# SOTB_Feb22.net
KiCad netlist of a schematic drawn in EAGLE
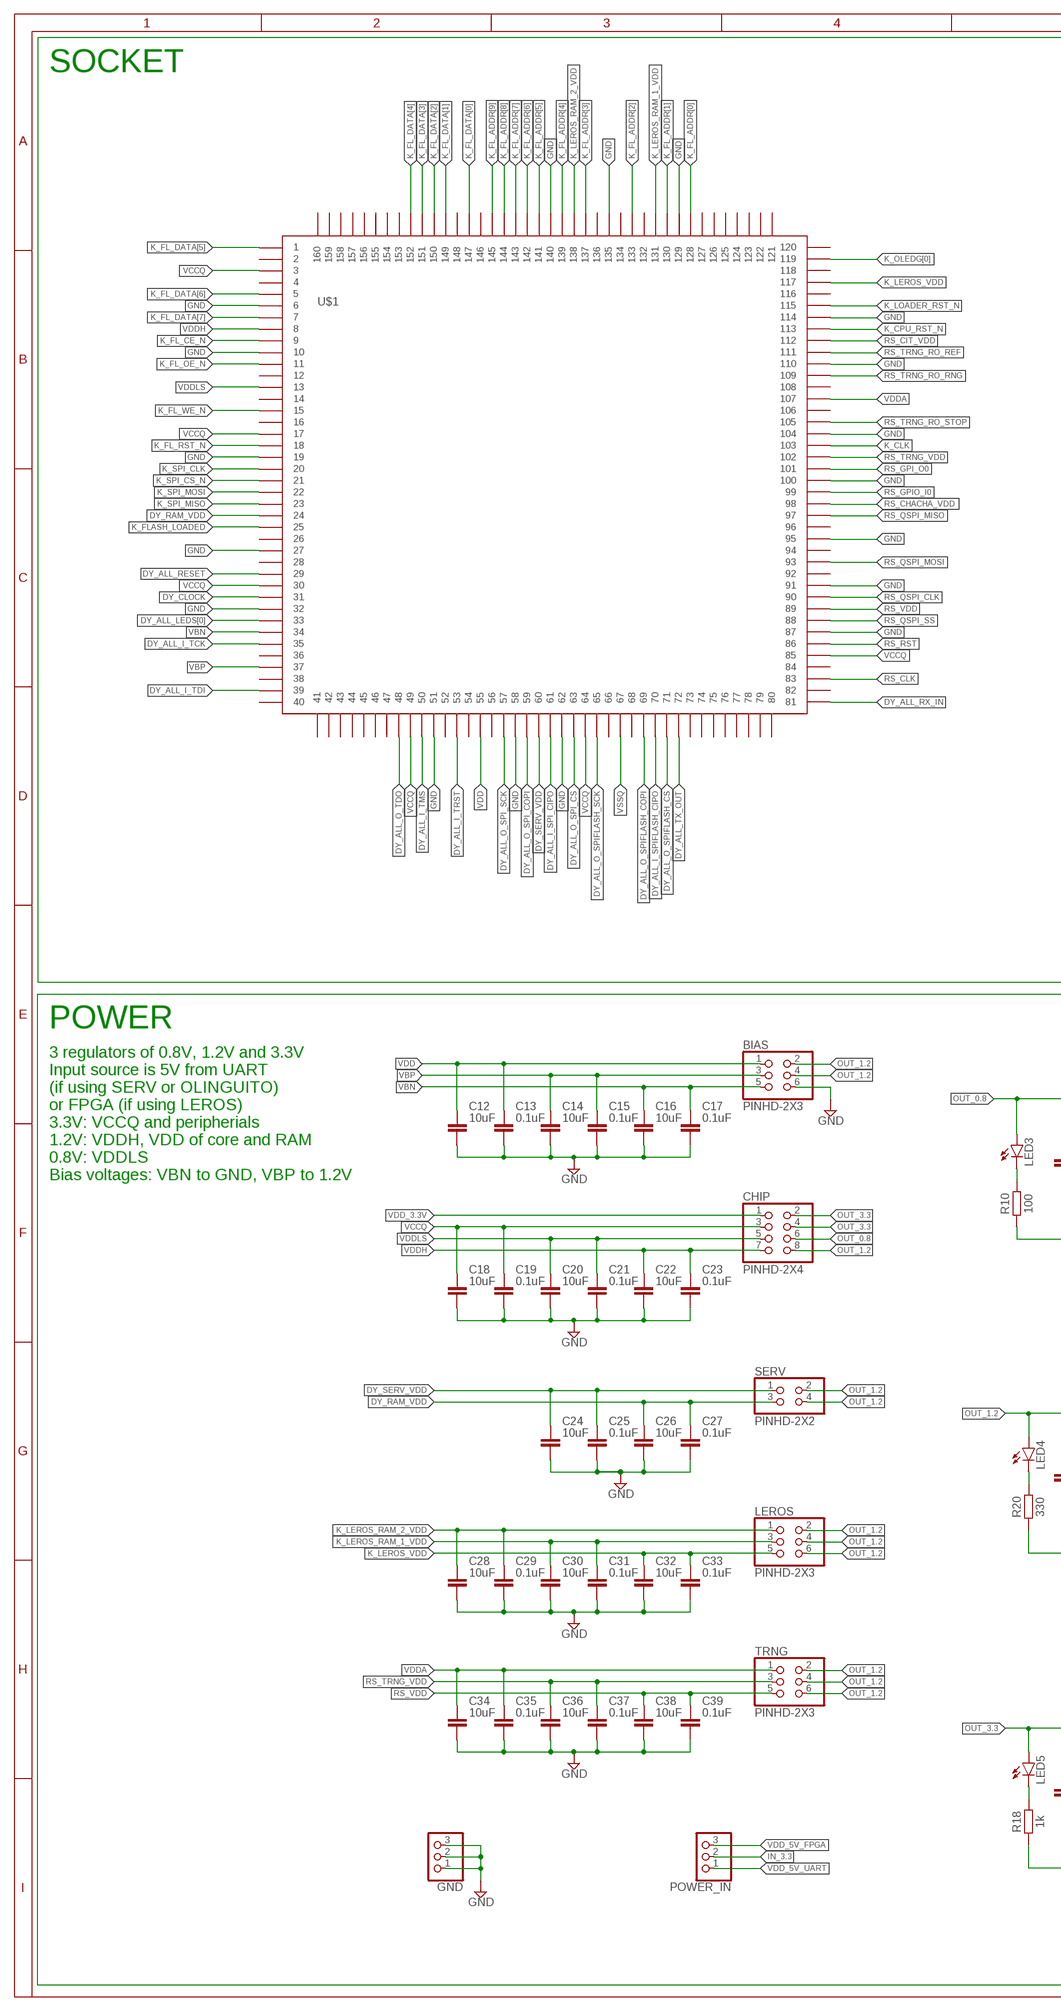
[diagram p0: schematic, sheet 1, part 1 of 2]
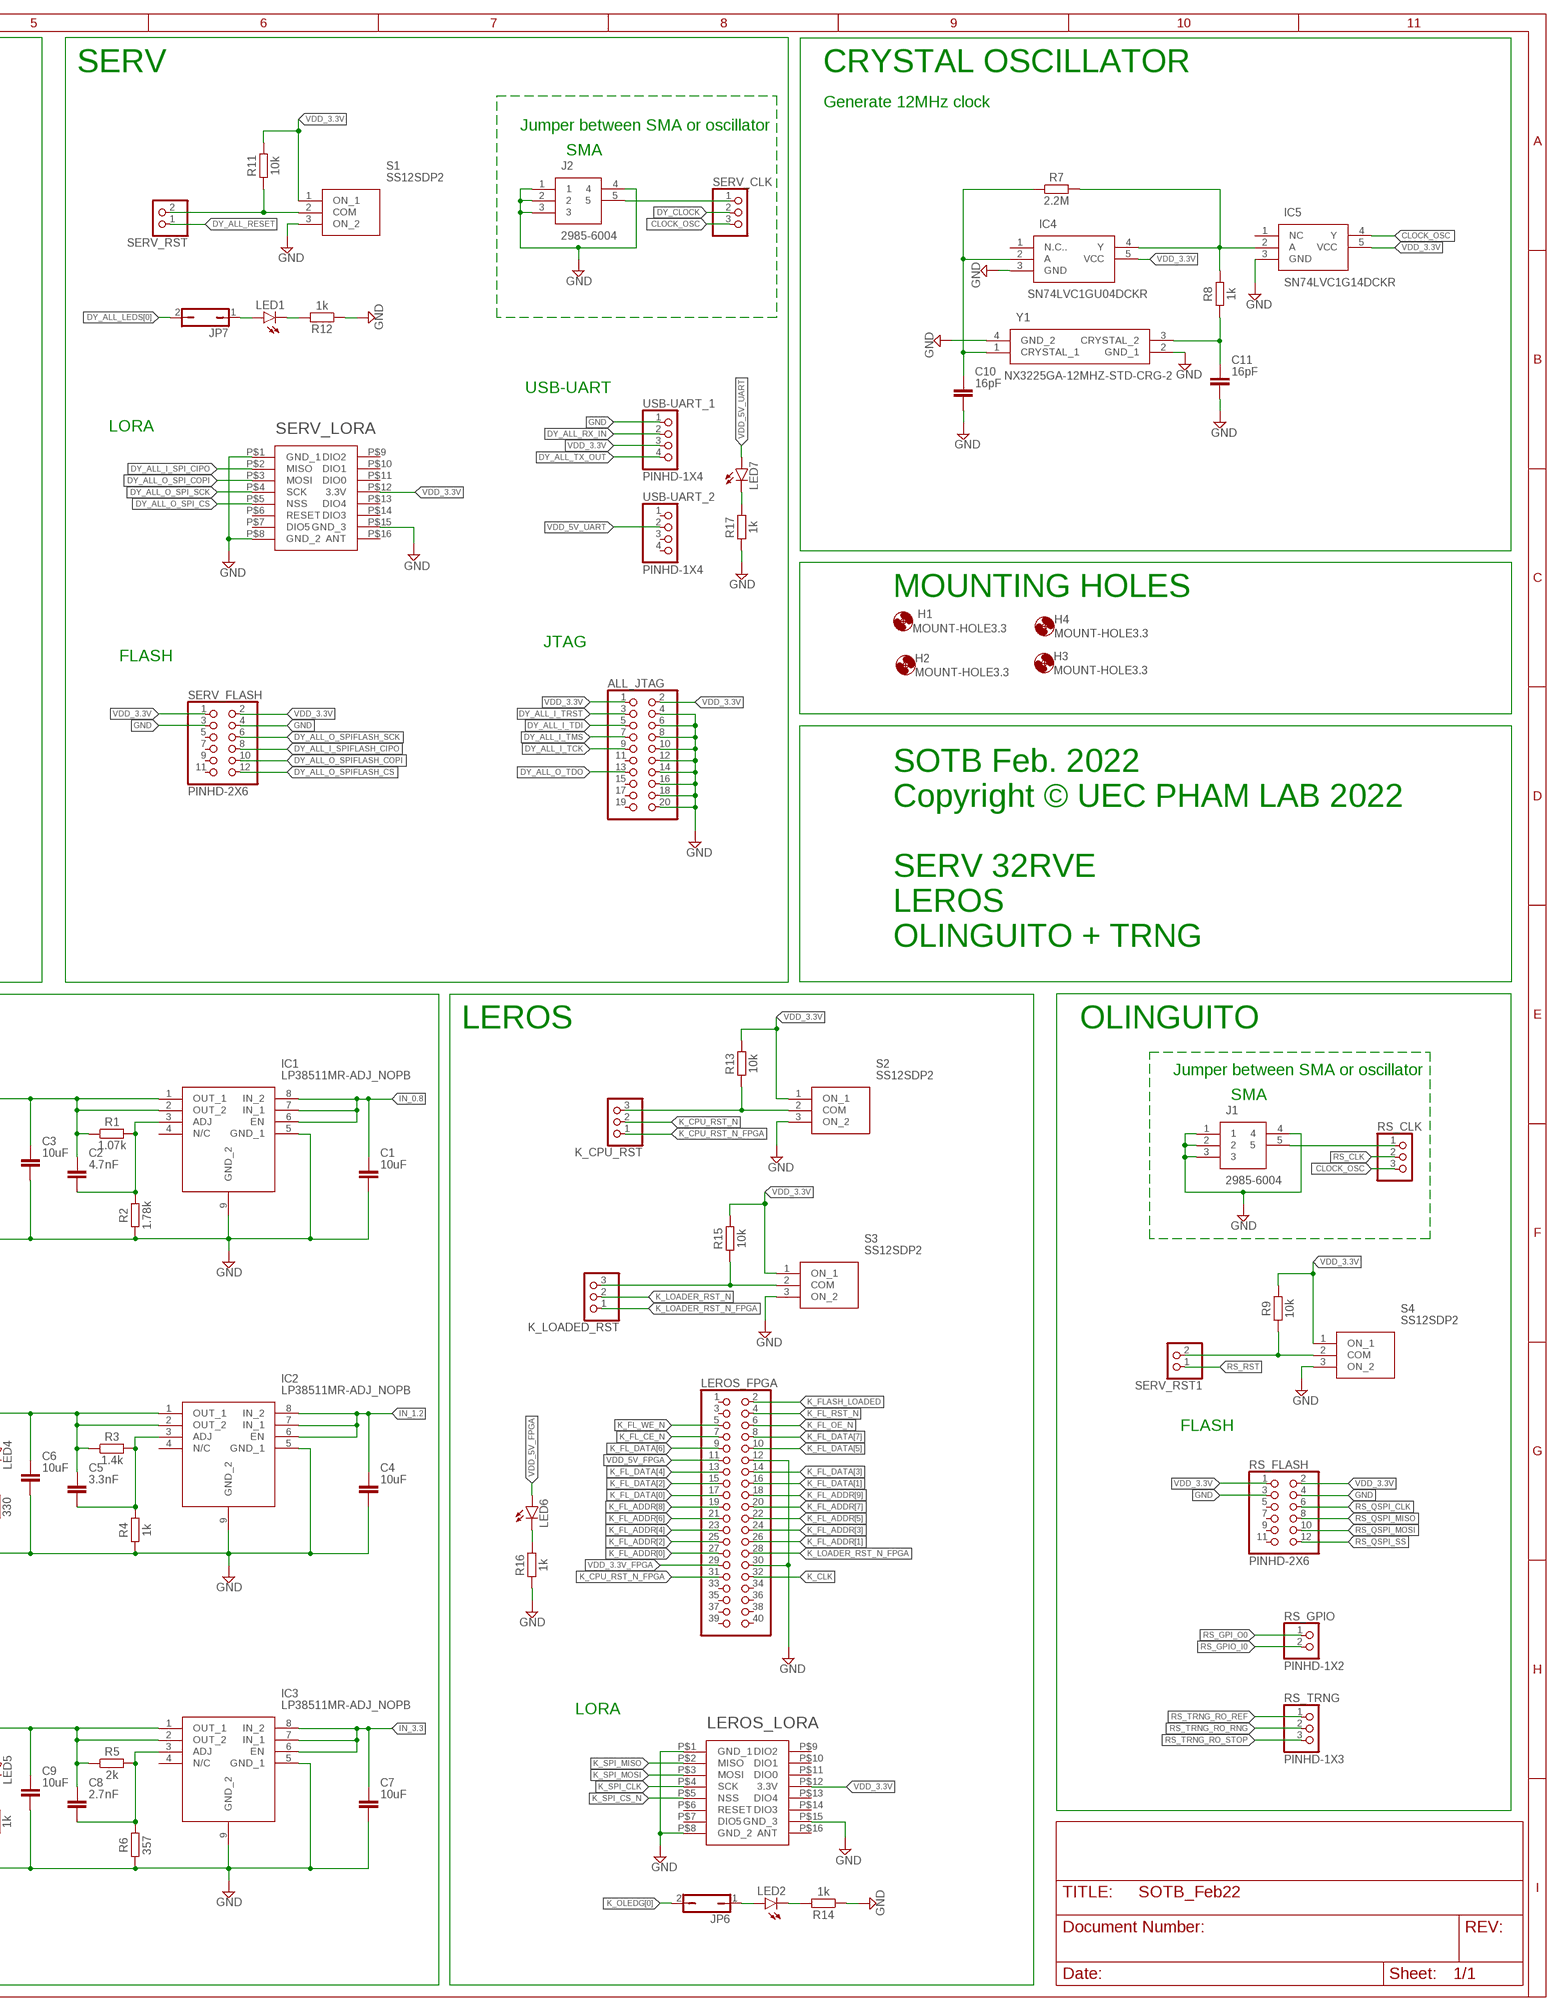
[diagram p1: schematic, sheet 1, part 2 of 2]

(export (version "E")
  (design (tool "Eeschema 10.0.6"))
  (components
    (comp (ref "ALL_JTAG")
      (value "PINHD-2X10")
      (footprint "eagle-import:2X10")
      (libsource (lib "eagle-import") (part "PINHD-2X10"))
    )
    (comp (ref "BIAS")
      (value "PINHD-2X3")
      (footprint "eagle-import:2X03")
      (libsource (lib "eagle-import") (part "PINHD-2X3"))
    )
    (comp (ref "C1")
      (value "10uF")
      (footprint "eagle-import:CAPC3216X135")
      (libsource (lib "eagle-import") (part "CCHIP-1206(3216-METRIC)_"))
    )
    (comp (ref "C2")
      (value "4.7nF")
      (footprint "eagle-import:CAPC3216X135")
      (libsource (lib "eagle-import") (part "CCHIP-1206(3216-METRIC)_"))
    )
    (comp (ref "C3")
      (value "10uF")
      (footprint "eagle-import:CAPC3216X135")
      (libsource (lib "eagle-import") (part "CCHIP-1206(3216-METRIC)_"))
    )
    (comp (ref "C4")
      (value "10uF")
      (footprint "eagle-import:CAPC3216X135")
      (libsource (lib "eagle-import") (part "CCHIP-1206(3216-METRIC)_"))
    )
    (comp (ref "C5")
      (value "3.3nF")
      (footprint "eagle-import:CAPC3216X135")
      (libsource (lib "eagle-import") (part "CCHIP-1206(3216-METRIC)_"))
    )
    (comp (ref "C6")
      (value "10uF")
      (footprint "eagle-import:CAPC3216X135")
      (libsource (lib "eagle-import") (part "CCHIP-1206(3216-METRIC)_"))
    )
    (comp (ref "C7")
      (value "10uF")
      (footprint "eagle-import:CAPC3216X135")
      (libsource (lib "eagle-import") (part "CCHIP-1206(3216-METRIC)_"))
    )
    (comp (ref "C8")
      (value "2.7nF")
      (footprint "eagle-import:CAPC3216X135")
      (libsource (lib "eagle-import") (part "CCHIP-1206(3216-METRIC)_"))
    )
    (comp (ref "C9")
      (value "10uF")
      (footprint "eagle-import:CAPC3216X135")
      (libsource (lib "eagle-import") (part "CCHIP-1206(3216-METRIC)_"))
    )
    (comp (ref "C10")
      (value "16pF")
      (footprint "eagle-import:CAPC3216X135")
      (libsource (lib "eagle-import") (part "CCHIP-1206(3216-METRIC)_"))
    )
    (comp (ref "C11")
      (value "16pF")
      (footprint "eagle-import:CAPC3216X135")
      (libsource (lib "eagle-import") (part "CCHIP-1206(3216-METRIC)_"))
    )
    (comp (ref "C12")
      (value "10uF")
      (footprint "eagle-import:CAPC3216X135")
      (libsource (lib "eagle-import") (part "CCHIP-1206(3216-METRIC)_"))
    )
    (comp (ref "C13")
      (value "0.1uF")
      (footprint "eagle-import:CAPC3216X135")
      (libsource (lib "eagle-import") (part "CCHIP-1206(3216-METRIC)_"))
    )
    (comp (ref "C14")
      (value "10uF")
      (footprint "eagle-import:CAPC3216X135")
      (libsource (lib "eagle-import") (part "CCHIP-1206(3216-METRIC)_"))
    )
    (comp (ref "C15")
      (value "0.1uF")
      (footprint "eagle-import:CAPC3216X135")
      (libsource (lib "eagle-import") (part "CCHIP-1206(3216-METRIC)_"))
    )
    (comp (ref "C16")
      (value "10uF")
      (footprint "eagle-import:CAPC3216X135")
      (libsource (lib "eagle-import") (part "CCHIP-1206(3216-METRIC)_"))
    )
    (comp (ref "C17")
      (value "0.1uF")
      (footprint "eagle-import:CAPC3216X135")
      (libsource (lib "eagle-import") (part "CCHIP-1206(3216-METRIC)_"))
    )
    (comp (ref "C18")
      (value "10uF")
      (footprint "eagle-import:CAPC3216X135")
      (libsource (lib "eagle-import") (part "CCHIP-1206(3216-METRIC)_"))
    )
    (comp (ref "C19")
      (value "0.1uF")
      (footprint "eagle-import:CAPC3216X135")
      (libsource (lib "eagle-import") (part "CCHIP-1206(3216-METRIC)_"))
    )
    (comp (ref "C20")
      (value "10uF")
      (footprint "eagle-import:CAPC3216X135")
      (libsource (lib "eagle-import") (part "CCHIP-1206(3216-METRIC)_"))
    )
    (comp (ref "C21")
      (value "0.1uF")
      (footprint "eagle-import:CAPC3216X135")
      (libsource (lib "eagle-import") (part "CCHIP-1206(3216-METRIC)_"))
    )
    (comp (ref "C22")
      (value "10uF")
      (footprint "eagle-import:CAPC3216X135")
      (libsource (lib "eagle-import") (part "CCHIP-1206(3216-METRIC)_"))
    )
    (comp (ref "C23")
      (value "0.1uF")
      (footprint "eagle-import:CAPC3216X135")
      (libsource (lib "eagle-import") (part "CCHIP-1206(3216-METRIC)_"))
    )
    (comp (ref "C24")
      (value "10uF")
      (footprint "eagle-import:CAPC3216X135")
      (libsource (lib "eagle-import") (part "CCHIP-1206(3216-METRIC)_"))
    )
    (comp (ref "C25")
      (value "0.1uF")
      (footprint "eagle-import:CAPC3216X135")
      (libsource (lib "eagle-import") (part "CCHIP-1206(3216-METRIC)_"))
    )
    (comp (ref "C26")
      (value "10uF")
      (footprint "eagle-import:CAPC3216X135")
      (libsource (lib "eagle-import") (part "CCHIP-1206(3216-METRIC)_"))
    )
    (comp (ref "C27")
      (value "0.1uF")
      (footprint "eagle-import:CAPC3216X135")
      (libsource (lib "eagle-import") (part "CCHIP-1206(3216-METRIC)_"))
    )
    (comp (ref "C28")
      (value "10uF")
      (footprint "eagle-import:CAPC3216X135")
      (libsource (lib "eagle-import") (part "CCHIP-1206(3216-METRIC)_"))
    )
    (comp (ref "C29")
      (value "0.1uF")
      (footprint "eagle-import:CAPC3216X135")
      (libsource (lib "eagle-import") (part "CCHIP-1206(3216-METRIC)_"))
    )
    (comp (ref "C30")
      (value "10uF")
      (footprint "eagle-import:CAPC3216X135")
      (libsource (lib "eagle-import") (part "CCHIP-1206(3216-METRIC)_"))
    )
    (comp (ref "C31")
      (value "0.1uF")
      (footprint "eagle-import:CAPC3216X135")
      (libsource (lib "eagle-import") (part "CCHIP-1206(3216-METRIC)_"))
    )
    (comp (ref "C32")
      (value "10uF")
      (footprint "eagle-import:CAPC3216X135")
      (libsource (lib "eagle-import") (part "CCHIP-1206(3216-METRIC)_"))
    )
    (comp (ref "C33")
      (value "0.1uF")
      (footprint "eagle-import:CAPC3216X135")
      (libsource (lib "eagle-import") (part "CCHIP-1206(3216-METRIC)_"))
    )
    (comp (ref "C34")
      (value "10uF")
      (footprint "eagle-import:CAPC3216X135")
      (libsource (lib "eagle-import") (part "CCHIP-1206(3216-METRIC)_"))
    )
    (comp (ref "C35")
      (value "0.1uF")
      (footprint "eagle-import:CAPC3216X135")
      (libsource (lib "eagle-import") (part "CCHIP-1206(3216-METRIC)_"))
    )
    (comp (ref "C36")
      (value "10uF")
      (footprint "eagle-import:CAPC3216X135")
      (libsource (lib "eagle-import") (part "CCHIP-1206(3216-METRIC)_"))
    )
    (comp (ref "C37")
      (value "0.1uF")
      (footprint "eagle-import:CAPC3216X135")
      (libsource (lib "eagle-import") (part "CCHIP-1206(3216-METRIC)_"))
    )
    (comp (ref "C38")
      (value "10uF")
      (footprint "eagle-import:CAPC3216X135")
      (libsource (lib "eagle-import") (part "CCHIP-1206(3216-METRIC)_"))
    )
    (comp (ref "C39")
      (value "0.1uF")
      (footprint "eagle-import:CAPC3216X135")
      (libsource (lib "eagle-import") (part "CCHIP-1206(3216-METRIC)_"))
    )
    (comp (ref "CHIP")
      (value "PINHD-2X4")
      (footprint "eagle-import:2X04")
      (libsource (lib "eagle-import") (part "PINHD-2X4"))
    )
    (comp (ref "GND")
      (value "PINHD-1X3")
      (footprint "eagle-import:1X03")
      (libsource (lib "eagle-import") (part "pinhead_325_PINHD-1X3"))
    )
    (comp (ref "H1")
      (value "MOUNT-HOLE3.3")
      (footprint "eagle-import:3,3")
      (libsource (lib "eagle-import") (part "MOUNT-HOLE3.3"))
    )
    (comp (ref "H2")
      (value "MOUNT-HOLE3.3")
      (footprint "eagle-import:3,3")
      (libsource (lib "eagle-import") (part "MOUNT-HOLE3.3"))
    )
    (comp (ref "H3")
      (value "MOUNT-HOLE3.3")
      (footprint "eagle-import:3,3")
      (libsource (lib "eagle-import") (part "MOUNT-HOLE3.3"))
    )
    (comp (ref "H4")
      (value "MOUNT-HOLE3.3")
      (footprint "eagle-import:3,3")
      (libsource (lib "eagle-import") (part "MOUNT-HOLE3.3"))
    )
    (comp (ref "IC1")
      (value "LP38511MR-ADJ_NOPB")
      (footprint "eagle-import:SOIC127P600X170-9N")
      (fields
        (field (name "ARROW_PART_NUMBER") "LP38511MR-ADJ/NOPB")
        (field (name "MOUSER_PART_NUMBER") "926-38511MR-ADJ/NOPB")
      )
      (libsource (lib "eagle-import") (part "LP38511MR-ADJ_NOPB"))
    )
    (comp (ref "IC2")
      (value "LP38511MR-ADJ_NOPB")
      (footprint "eagle-import:SOIC127P600X170-9N")
      (fields
        (field (name "ARROW_PART_NUMBER") "LP38511MR-ADJ/NOPB")
        (field (name "MOUSER_PART_NUMBER") "926-38511MR-ADJ/NOPB")
      )
      (libsource (lib "eagle-import") (part "LP38511MR-ADJ_NOPB"))
    )
    (comp (ref "IC3")
      (value "LP38511MR-ADJ_NOPB")
      (footprint "eagle-import:SOIC127P600X170-9N")
      (fields
        (field (name "ARROW_PART_NUMBER") "LP38511MR-ADJ/NOPB")
        (field (name "MOUSER_PART_NUMBER") "926-38511MR-ADJ/NOPB")
      )
      (libsource (lib "eagle-import") (part "LP38511MR-ADJ_NOPB"))
    )
    (comp (ref "IC4")
      (value "SN74LVC1GU04DCKR")
      (footprint "eagle-import:SOT65P210X110-5N")
      (fields (field (name "MOUSER_PART_NUMBER") "595-SN74LVC1GU04DCKR"))
      (libsource (lib "eagle-import") (part "SN74LVC1GU04DCKR"))
    )
    (comp (ref "IC5")
      (value "SN74LVC1G14DCKR")
      (footprint "eagle-import:SOT65P210X110-5N")
      (fields (field (name "MOUSER_PART_NUMBER") "595-SN74LVC1G14DCKR"))
      (libsource (lib "eagle-import") (part "SN74LVC1G14DCKR"))
    )
    (comp (ref "J1")
      (value "2985-6004")
      (footprint "eagle-import:29856004")
      (fields (field (name "MOUSER_PART_NUMBER") "523-2985-6004"))
      (libsource (lib "eagle-import") (part "2985-6004"))
    )
    (comp (ref "J2")
      (value "2985-6004")
      (footprint "eagle-import:29856004")
      (fields (field (name "MOUSER_PART_NUMBER") "523-2985-6004"))
      (libsource (lib "eagle-import") (part "2985-6004"))
    )
    (comp (ref "JP6")
      (value "JP1Q")
      (footprint "eagle-import:JP1")
      (libsource (lib "eagle-import") (part "JP1Q"))
    )
    (comp (ref "JP7")
      (value "JP1Q")
      (footprint "eagle-import:JP1")
      (libsource (lib "eagle-import") (part "JP1Q"))
    )
    (comp (ref "K_CPU_RST")
      (value "PINHD-1X3")
      (footprint "eagle-import:1X03")
      (libsource (lib "eagle-import") (part "pinhead_325_PINHD-1X3"))
    )
    (comp (ref "K_LOADED_RST")
      (value "PINHD-1X3")
      (footprint "eagle-import:1X03")
      (libsource (lib "eagle-import") (part "pinhead_325_PINHD-1X3"))
    )
    (comp (ref "LED1")
      (value "LEDCHIPLED_1206")
      (footprint "eagle-import:CHIPLED_1206")
      (libsource (lib "eagle-import") (part "LEDCHIPLED_1206"))
    )
    (comp (ref "LED2")
      (value "LEDCHIPLED_1206")
      (footprint "eagle-import:CHIPLED_1206")
      (libsource (lib "eagle-import") (part "LEDCHIPLED_1206"))
    )
    (comp (ref "LED3")
      (value "LEDCHIPLED_1206")
      (footprint "eagle-import:CHIPLED_1206")
      (libsource (lib "eagle-import") (part "LEDCHIPLED_1206"))
    )
    (comp (ref "LED4")
      (value "LEDCHIPLED_1206")
      (footprint "eagle-import:CHIPLED_1206")
      (libsource (lib "eagle-import") (part "LEDCHIPLED_1206"))
    )
    (comp (ref "LED5")
      (value "LEDCHIPLED_1206")
      (footprint "eagle-import:CHIPLED_1206")
      (libsource (lib "eagle-import") (part "LEDCHIPLED_1206"))
    )
    (comp (ref "LED6")
      (value "LEDCHIPLED_1206")
      (footprint "eagle-import:CHIPLED_1206")
      (libsource (lib "eagle-import") (part "LEDCHIPLED_1206"))
    )
    (comp (ref "LED7")
      (value "LEDCHIPLED_1206")
      (footprint "eagle-import:CHIPLED_1206")
      (libsource (lib "eagle-import") (part "LEDCHIPLED_1206"))
    )
    (comp (ref "LEROS")
      (value "PINHD-2X3")
      (footprint "eagle-import:2X03")
      (libsource (lib "eagle-import") (part "PINHD-2X3"))
    )
    (comp (ref "LEROS_FPGA")
      (value "PINHD-2X20")
      (footprint "eagle-import:2X20")
      (libsource (lib "eagle-import") (part "PINHD-2X20"))
    )
    (comp (ref "LEROS_LORA")
      (value "RFM95W-915S2")
      (footprint "eagle-import:RFM95W-915S2")
      (libsource (lib "eagle-import") (part "RFM95W-915S2"))
    )
    (comp (ref "POWER_IN")
      (value "PINHD-1X3")
      (footprint "eagle-import:1X03")
      (libsource (lib "eagle-import") (part "pinhead_325_PINHD-1X3"))
    )
    (comp (ref "R1")
      (value "1.07k")
      (footprint "eagle-import:RESC3216X70")
      (libsource (lib "eagle-import") (part "RCHIP-1206(3216-METRIC)_"))
    )
    (comp (ref "R2")
      (value "1.78k")
      (footprint "eagle-import:RESC3216X70")
      (libsource (lib "eagle-import") (part "RCHIP-1206(3216-METRIC)_"))
    )
    (comp (ref "R3")
      (value "1.4k")
      (footprint "eagle-import:RESC3216X70")
      (libsource (lib "eagle-import") (part "RCHIP-1206(3216-METRIC)_"))
    )
    (comp (ref "R4")
      (value "1k")
      (footprint "eagle-import:RESC3216X70")
      (libsource (lib "eagle-import") (part "RCHIP-1206(3216-METRIC)_"))
    )
    (comp (ref "R5")
      (value "2k")
      (footprint "eagle-import:RESC3216X70")
      (libsource (lib "eagle-import") (part "RCHIP-1206(3216-METRIC)_"))
    )
    (comp (ref "R6")
      (value "357")
      (footprint "eagle-import:RESC3216X70")
      (libsource (lib "eagle-import") (part "RCHIP-1206(3216-METRIC)_"))
    )
    (comp (ref "R7")
      (value "2.2M")
      (footprint "eagle-import:RESC3216X70")
      (libsource (lib "eagle-import") (part "RCHIP-1206(3216-METRIC)_"))
    )
    (comp (ref "R8")
      (value "1k")
      (footprint "eagle-import:RESC3216X70")
      (libsource (lib "eagle-import") (part "RCHIP-1206(3216-METRIC)_"))
    )
    (comp (ref "R9")
      (value "10k")
      (footprint "eagle-import:RESC3216X70")
      (libsource (lib "eagle-import") (part "RCHIP-1206(3216-METRIC)_"))
    )
    (comp (ref "R10")
      (value "100")
      (footprint "eagle-import:RESC3216X70")
      (libsource (lib "eagle-import") (part "RCHIP-1206(3216-METRIC)_"))
    )
    (comp (ref "R11")
      (value "10k")
      (footprint "eagle-import:RESC3216X70")
      (libsource (lib "eagle-import") (part "RCHIP-1206(3216-METRIC)_"))
    )
    (comp (ref "R12")
      (value "1k")
      (footprint "eagle-import:RESC3216X70")
      (libsource (lib "eagle-import") (part "RCHIP-1206(3216-METRIC)_"))
    )
    (comp (ref "R13")
      (value "10k")
      (footprint "eagle-import:RESC3216X70")
      (libsource (lib "eagle-import") (part "RCHIP-1206(3216-METRIC)_"))
    )
    (comp (ref "R14")
      (value "1k")
      (footprint "eagle-import:RESC3216X70")
      (libsource (lib "eagle-import") (part "RCHIP-1206(3216-METRIC)_"))
    )
    (comp (ref "R15")
      (value "10k")
      (footprint "eagle-import:RESC3216X70")
      (libsource (lib "eagle-import") (part "RCHIP-1206(3216-METRIC)_"))
    )
    (comp (ref "R16")
      (value "1k")
      (footprint "eagle-import:RESC3216X70")
      (libsource (lib "eagle-import") (part "RCHIP-1206(3216-METRIC)_"))
    )
    (comp (ref "R17")
      (value "1k")
      (footprint "eagle-import:RESC3216X70")
      (libsource (lib "eagle-import") (part "RCHIP-1206(3216-METRIC)_"))
    )
    (comp (ref "R18")
      (value "1k")
      (footprint "eagle-import:RESC3216X70")
      (libsource (lib "eagle-import") (part "RCHIP-1206(3216-METRIC)_"))
    )
    (comp (ref "R20")
      (value "330")
      (footprint "eagle-import:RESC3216X70")
      (libsource (lib "eagle-import") (part "RCHIP-1206(3216-METRIC)_"))
    )
    (comp (ref "RS_CLK")
      (value "PINHD-1X3")
      (footprint "eagle-import:1X03")
      (libsource (lib "eagle-import") (part "pinhead_325_PINHD-1X3"))
    )
    (comp (ref "RS_FLASH")
      (value "PINHD-2X6")
      (footprint "eagle-import:2X06")
      (libsource (lib "eagle-import") (part "PINHD-2X6"))
    )
    (comp (ref "RS_GPIO")
      (value "PINHD-1X2")
      (footprint "eagle-import:1X02")
      (libsource (lib "eagle-import") (part "PINHD-1X2"))
    )
    (comp (ref "RS_TRNG")
      (value "PINHD-1X3")
      (footprint "eagle-import:1X03")
      (libsource (lib "eagle-import") (part "PINHD-1X3"))
    )
    (comp (ref "S1")
      (value "SS12SDP2")
      (footprint "eagle-import:SS12SDP2")
      (fields (field (name "MOUSER_PART_NUMBER") "633-SS12SDP2"))
      (libsource (lib "eagle-import") (part "SS12SDP2"))
    )
    (comp (ref "S2")
      (value "SS12SDP2")
      (footprint "eagle-import:SS12SDP2")
      (fields (field (name "MOUSER_PART_NUMBER") "633-SS12SDP2"))
      (libsource (lib "eagle-import") (part "SS12SDP2"))
    )
    (comp (ref "S3")
      (value "SS12SDP2")
      (footprint "eagle-import:SS12SDP2")
      (fields (field (name "MOUSER_PART_NUMBER") "633-SS12SDP2"))
      (libsource (lib "eagle-import") (part "SS12SDP2"))
    )
    (comp (ref "S4")
      (value "SS12SDP2")
      (footprint "eagle-import:SS12SDP2")
      (fields (field (name "MOUSER_PART_NUMBER") "633-SS12SDP2"))
      (libsource (lib "eagle-import") (part "SS12SDP2"))
    )
    (comp (ref "SERV")
      (value "PINHD-2X2")
      (footprint "eagle-import:2X02")
      (libsource (lib "eagle-import") (part "PINHD-2X2"))
    )
    (comp (ref "SERV_CLK")
      (value "PINHD-1X3")
      (footprint "eagle-import:1X03")
      (libsource (lib "eagle-import") (part "pinhead_325_PINHD-1X3"))
    )
    (comp (ref "SERV_FLASH")
      (value "PINHD-2X6")
      (footprint "eagle-import:2X06")
      (libsource (lib "eagle-import") (part "PINHD-2X6"))
    )
    (comp (ref "SERV_LORA")
      (value "RFM95W-915S2")
      (footprint "eagle-import:RFM95W-915S2")
      (libsource (lib "eagle-import") (part "RFM95W-915S2"))
    )
    (comp (ref "SERV_RST")
      (value "PINHD-1X2")
      (footprint "eagle-import:1X02")
      (libsource (lib "eagle-import") (part "pinhead_325_PINHD-1X2"))
    )
    (comp (ref "SERV_RST1")
      (value "PINHD-1X2")
      (footprint "eagle-import:1X02")
      (libsource (lib "eagle-import") (part "pinhead_325_PINHD-1X2"))
    )
    (comp (ref "TRNG")
      (value "PINHD-2X3")
      (footprint "eagle-import:2X03")
      (libsource (lib "eagle-import") (part "PINHD-2X3"))
    )
    (comp (ref "U$1")
      (value "QFP28-160PIN")
      (footprint "eagle-import:QFP28-160PIN")
      (libsource (lib "eagle-import") (part "QFP28-160PIN"))
    )
    (comp (ref "USB-UART_1")
      (value "PINHD-1X4")
      (footprint "eagle-import:1X04")
      (libsource (lib "eagle-import") (part "PINHD-1X4"))
    )
    (comp (ref "USB-UART_2")
      (value "PINHD-1X4")
      (footprint "eagle-import:1X04")
      (libsource (lib "eagle-import") (part "PINHD-1X4"))
    )
    (comp (ref "Y1")
      (value "NX3225GA-12MHZ-STD-CRG-2")
      (footprint "eagle-import:NX3225GA12MHZSTDCRG2")
      (fields (field (name "MOUSER_PART_NUMBER") "344-NX3225GA12STCRG2"))
      (libsource (lib "eagle-import") (part "NX3225GA-12MHZ-STD-CRG-2"))
    )
  )
  (nets
    (net (code "1") (name "CLOCK_OSC") (class "Default")
      (node (ref "IC5") (pin "4") (pinfunction "Y_4") (pintype "bidirectional"))
      (node (ref "RS_CLK") (pin "3") (pinfunction "3_3") (pintype "passive"))
      (node (ref "SERV_CLK") (pin "3") (pinfunction "3_3") (pintype "passive"))
    )
    (net (code "2") (name "DY_ALL_I_SPIFLASH_CIPO") (class "Default")
      (node (ref "SERV_FLASH") (pin "8") (pinfunction "8_8") (pintype "passive"))
      (node (ref "U$1") (pin "P$70") (pinfunction "70_P$70") (pintype "bidirectional"))
    )
    (net (code "3") (name "DY_ALL_I_SPI_CIPO") (class "Default")
      (node (ref "SERV_LORA") (pin "P$2") (pinfunction "MISO_P$2") (pintype "bidirectional"))
      (node (ref "U$1") (pin "P$61") (pinfunction "61_P$61") (pintype "bidirectional"))
    )
    (net (code "4") (name "DY_ALL_I_TCK") (class "Default")
      (node (ref "ALL_JTAG") (pin "9") (pinfunction "9_9") (pintype "passive"))
      (node (ref "U$1") (pin "P$35") (pinfunction "35_P$35") (pintype "bidirectional"))
    )
    (net (code "5") (name "DY_ALL_I_TDI") (class "Default")
      (node (ref "ALL_JTAG") (pin "5") (pinfunction "5_5") (pintype "passive"))
      (node (ref "U$1") (pin "P$39") (pinfunction "39_P$39") (pintype "bidirectional"))
    )
    (net (code "6") (name "DY_ALL_I_TMS") (class "Default")
      (node (ref "ALL_JTAG") (pin "7") (pinfunction "7_7") (pintype "passive"))
      (node (ref "U$1") (pin "P$50") (pinfunction "50_P$50") (pintype "bidirectional"))
    )
    (net (code "7") (name "DY_ALL_I_TRST") (class "Default")
      (node (ref "ALL_JTAG") (pin "3") (pinfunction "3_3") (pintype "passive"))
      (node (ref "U$1") (pin "P$53") (pinfunction "53_P$53") (pintype "bidirectional"))
    )
    (net (code "8") (name "DY_ALL_LEDS[0]") (class "Default")
      (node (ref "JP7") (pin "2") (pinfunction "2_2") (pintype "passive"))
      (node (ref "U$1") (pin "P$33") (pinfunction "33_P$33") (pintype "bidirectional"))
    )
    (net (code "9") (name "DY_ALL_O_SPIFLASH_COPI") (class "Default")
      (node (ref "SERV_FLASH") (pin "10") (pinfunction "10_10") (pintype "passive"))
      (node (ref "U$1") (pin "P$69") (pinfunction "69_P$69") (pintype "bidirectional"))
    )
    (net (code "10") (name "DY_ALL_O_SPIFLASH_CS") (class "Default")
      (node (ref "SERV_FLASH") (pin "12") (pinfunction "12_12") (pintype "passive"))
      (node (ref "U$1") (pin "P$71") (pinfunction "71_P$71") (pintype "bidirectional"))
    )
    (net (code "11") (name "DY_ALL_O_SPIFLASH_SCK") (class "Default")
      (node (ref "SERV_FLASH") (pin "6") (pinfunction "6_6") (pintype "passive"))
      (node (ref "U$1") (pin "P$65") (pinfunction "65_P$65") (pintype "bidirectional"))
    )
    (net (code "12") (name "DY_ALL_O_SPI_COPI") (class "Default")
      (node (ref "SERV_LORA") (pin "P$3") (pinfunction "MOSI_P$3") (pintype "bidirectional"))
      (node (ref "U$1") (pin "P$59") (pinfunction "59_P$59") (pintype "bidirectional"))
    )
    (net (code "13") (name "DY_ALL_O_SPI_CS") (class "Default")
      (node (ref "SERV_LORA") (pin "P$5") (pinfunction "NSS_P$5") (pintype "bidirectional"))
      (node (ref "U$1") (pin "P$63") (pinfunction "63_P$63") (pintype "bidirectional"))
    )
    (net (code "14") (name "DY_ALL_O_SPI_SCK") (class "Default")
      (node (ref "SERV_LORA") (pin "P$4") (pinfunction "SCK_P$4") (pintype "bidirectional"))
      (node (ref "U$1") (pin "P$57") (pinfunction "57_P$57") (pintype "bidirectional"))
    )
    (net (code "15") (name "DY_ALL_O_TDO") (class "Default")
      (node (ref "ALL_JTAG") (pin "13") (pinfunction "13_13") (pintype "passive"))
      (node (ref "U$1") (pin "P$48") (pinfunction "48_P$48") (pintype "bidirectional"))
    )
    (net (code "16") (name "DY_ALL_RESET") (class "Default")
      (node (ref "SERV_RST") (pin "1") (pinfunction "1_1") (pintype "passive"))
      (node (ref "U$1") (pin "P$29") (pinfunction "29_P$29") (pintype "bidirectional"))
    )
    (net (code "17") (name "DY_ALL_RX_IN") (class "Default")
      (node (ref "U$1") (pin "P$81") (pinfunction "81_P$81") (pintype "bidirectional"))
      (node (ref "USB-UART_1") (pin "2") (pinfunction "2_2") (pintype "passive"))
    )
    (net (code "18") (name "DY_ALL_TX_OUT") (class "Default")
      (node (ref "U$1") (pin "P$72") (pinfunction "72_P$72") (pintype "bidirectional"))
      (node (ref "USB-UART_1") (pin "4") (pinfunction "4_4") (pintype "passive"))
    )
    (net (code "19") (name "DY_CLOCK") (class "Default")
      (node (ref "SERV_CLK") (pin "2") (pinfunction "2_2") (pintype "passive"))
      (node (ref "U$1") (pin "P$31") (pinfunction "31_P$31") (pintype "bidirectional"))
    )
    (net (code "20") (name "DY_RAM_VDD") (class "Default")
      (node (ref "C26") (pin "1") (pinfunction "1_1") (pintype "passive"))
      (node (ref "C27") (pin "1") (pinfunction "1_1") (pintype "passive"))
      (node (ref "SERV") (pin "3") (pinfunction "3_3") (pintype "passive"))
      (node (ref "U$1") (pin "P$24") (pinfunction "24_P$24") (pintype "bidirectional"))
    )
    (net (code "21") (name "DY_SERV_VDD") (class "Default")
      (node (ref "C24") (pin "1") (pinfunction "1_1") (pintype "passive"))
      (node (ref "C25") (pin "1") (pinfunction "1_1") (pintype "passive"))
      (node (ref "SERV") (pin "1") (pinfunction "1_1") (pintype "passive"))
      (node (ref "U$1") (pin "P$60") (pinfunction "60_P$60") (pintype "bidirectional"))
    )
    (net (code "22") (name "GND") (class "Default")
      (node (ref "ALL_JTAG") (pin "10") (pinfunction "10_10") (pintype "passive"))
      (node (ref "ALL_JTAG") (pin "12") (pinfunction "12_12") (pintype "passive"))
      (node (ref "ALL_JTAG") (pin "14") (pinfunction "14_14") (pintype "passive"))
      (node (ref "ALL_JTAG") (pin "16") (pinfunction "16_16") (pintype "passive"))
      (node (ref "ALL_JTAG") (pin "18") (pinfunction "18_18") (pintype "passive"))
      (node (ref "ALL_JTAG") (pin "20") (pinfunction "20_20") (pintype "passive"))
      (node (ref "ALL_JTAG") (pin "4") (pinfunction "4_4") (pintype "passive"))
      (node (ref "ALL_JTAG") (pin "6") (pinfunction "6_6") (pintype "passive"))
      (node (ref "ALL_JTAG") (pin "8") (pinfunction "8_8") (pintype "passive"))
      (node (ref "BIAS") (pin "6") (pinfunction "6_6") (pintype "passive"))
      (node (ref "C1") (pin "2") (pinfunction "2_2") (pintype "passive"))
      (node (ref "C10") (pin "2") (pinfunction "2_2") (pintype "passive"))
      (node (ref "C11") (pin "2") (pinfunction "2_2") (pintype "passive"))
      (node (ref "C12") (pin "2") (pinfunction "2_2") (pintype "passive"))
      (node (ref "C13") (pin "2") (pinfunction "2_2") (pintype "passive"))
      (node (ref "C14") (pin "2") (pinfunction "2_2") (pintype "passive"))
      (node (ref "C15") (pin "2") (pinfunction "2_2") (pintype "passive"))
      (node (ref "C16") (pin "2") (pinfunction "2_2") (pintype "passive"))
      (node (ref "C17") (pin "2") (pinfunction "2_2") (pintype "passive"))
      (node (ref "C18") (pin "2") (pinfunction "2_2") (pintype "passive"))
      (node (ref "C19") (pin "2") (pinfunction "2_2") (pintype "passive"))
      (node (ref "C20") (pin "2") (pinfunction "2_2") (pintype "passive"))
      (node (ref "C21") (pin "2") (pinfunction "2_2") (pintype "passive"))
      (node (ref "C22") (pin "2") (pinfunction "2_2") (pintype "passive"))
      (node (ref "C23") (pin "2") (pinfunction "2_2") (pintype "passive"))
      (node (ref "C24") (pin "2") (pinfunction "2_2") (pintype "passive"))
      (node (ref "C25") (pin "2") (pinfunction "2_2") (pintype "passive"))
      (node (ref "C26") (pin "2") (pinfunction "2_2") (pintype "passive"))
      (node (ref "C27") (pin "2") (pinfunction "2_2") (pintype "passive"))
      (node (ref "C28") (pin "2") (pinfunction "2_2") (pintype "passive"))
      (node (ref "C29") (pin "2") (pinfunction "2_2") (pintype "passive"))
      (node (ref "C3") (pin "2") (pinfunction "2_2") (pintype "passive"))
      (node (ref "C30") (pin "2") (pinfunction "2_2") (pintype "passive"))
      (node (ref "C31") (pin "2") (pinfunction "2_2") (pintype "passive"))
      (node (ref "C32") (pin "2") (pinfunction "2_2") (pintype "passive"))
      (node (ref "C33") (pin "2") (pinfunction "2_2") (pintype "passive"))
      (node (ref "C34") (pin "2") (pinfunction "2_2") (pintype "passive"))
      (node (ref "C35") (pin "2") (pinfunction "2_2") (pintype "passive"))
      (node (ref "C36") (pin "2") (pinfunction "2_2") (pintype "passive"))
      (node (ref "C37") (pin "2") (pinfunction "2_2") (pintype "passive"))
      (node (ref "C38") (pin "2") (pinfunction "2_2") (pintype "passive"))
      (node (ref "C39") (pin "2") (pinfunction "2_2") (pintype "passive"))
      (node (ref "C4") (pin "2") (pinfunction "2_2") (pintype "passive"))
      (node (ref "C6") (pin "2") (pinfunction "2_2") (pintype "passive"))
      (node (ref "C7") (pin "2") (pinfunction "2_2") (pintype "passive"))
      (node (ref "C9") (pin "2") (pinfunction "2_2") (pintype "passive"))
      (node (ref "GND") (pin "1") (pinfunction "1_1") (pintype "passive"))
      (node (ref "GND") (pin "2") (pinfunction "2_2") (pintype "passive"))
      (node (ref "GND") (pin "3") (pinfunction "3_3") (pintype "passive"))
      (node (ref "IC1") (pin "5") (pinfunction "GND_1_5") (pintype "bidirectional"))
      (node (ref "IC1") (pin "9") (pinfunction "GND_2_9") (pintype "bidirectional"))
      (node (ref "IC2") (pin "5") (pinfunction "GND_1_5") (pintype "bidirectional"))
      (node (ref "IC2") (pin "9") (pinfunction "GND_2_9") (pintype "bidirectional"))
      (node (ref "IC3") (pin "5") (pinfunction "GND_1_5") (pintype "bidirectional"))
      (node (ref "IC3") (pin "9") (pinfunction "GND_2_9") (pintype "bidirectional"))
      (node (ref "IC4") (pin "3") (pinfunction "GND_3") (pintype "bidirectional"))
      (node (ref "IC5") (pin "3") (pinfunction "GND_3") (pintype "power_in"))
      (node (ref "J1") (pin "1") (pinfunction "1_1") (pintype "bidirectional"))
      (node (ref "J1") (pin "2") (pinfunction "2_2") (pintype "bidirectional"))
      (node (ref "J1") (pin "3") (pinfunction "3_3") (pintype "bidirectional"))
      (node (ref "J1") (pin "4") (pinfunction "4_4") (pintype "bidirectional"))
      (node (ref "J2") (pin "1") (pinfunction "1_1") (pintype "bidirectional"))
      (node (ref "J2") (pin "2") (pinfunction "2_2") (pintype "bidirectional"))
      (node (ref "J2") (pin "3") (pinfunction "3_3") (pintype "bidirectional"))
      (node (ref "J2") (pin "4") (pinfunction "4_4") (pintype "bidirectional"))
      (node (ref "LEROS_FPGA") (pin "12") (pinfunction "12_12") (pintype "passive"))
      (node (ref "LEROS_FPGA") (pin "30") (pinfunction "30_30") (pintype "passive"))
      (node (ref "LEROS_LORA") (pin "P$1") (pinfunction "GND_1_P$1") (pintype "bidirectional"))
      (node (ref "LEROS_LORA") (pin "P$15") (pinfunction "GND_3_P$15") (pintype "bidirectional"))
      (node (ref "LEROS_LORA") (pin "P$8") (pinfunction "GND_2_P$8") (pintype "bidirectional"))
      (node (ref "R10") (pin "1") (pinfunction "1_1") (pintype "passive"))
      (node (ref "R12") (pin "1") (pinfunction "1_1") (pintype "passive"))
      (node (ref "R14") (pin "1") (pinfunction "1_1") (pintype "passive"))
      (node (ref "R16") (pin "1") (pinfunction "1_1") (pintype "passive"))
      (node (ref "R17") (pin "1") (pinfunction "1_1") (pintype "passive"))
      (node (ref "R18") (pin "1") (pinfunction "1_1") (pintype "passive"))
      (node (ref "R2") (pin "1") (pinfunction "1_1") (pintype "passive"))
      (node (ref "R20") (pin "1") (pinfunction "1_1") (pintype "passive"))
      (node (ref "R4") (pin "1") (pinfunction "1_1") (pintype "passive"))
      (node (ref "R6") (pin "1") (pinfunction "1_1") (pintype "passive"))
      (node (ref "RS_FLASH") (pin "3") (pinfunction "3_3") (pintype "passive"))
      (node (ref "RS_FLASH") (pin "4") (pinfunction "4_4") (pintype "passive"))
      (node (ref "S1") (pin "3") (pinfunction "ON_2_3") (pintype "bidirectional"))
      (node (ref "S2") (pin "3") (pinfunction "ON_2_3") (pintype "bidirectional"))
      (node (ref "S3") (pin "3") (pinfunction "ON_2_3") (pintype "bidirectional"))
      (node (ref "S4") (pin "3") (pinfunction "ON_2_3") (pintype "bidirectional"))
      (node (ref "SERV_FLASH") (pin "3") (pinfunction "3_3") (pintype "passive"))
      (node (ref "SERV_FLASH") (pin "4") (pinfunction "4_4") (pintype "passive"))
      (node (ref "SERV_LORA") (pin "P$1") (pinfunction "GND_1_P$1") (pintype "bidirectional"))
      (node (ref "SERV_LORA") (pin "P$15") (pinfunction "GND_3_P$15") (pintype "bidirectional"))
      (node (ref "SERV_LORA") (pin "P$8") (pinfunction "GND_2_P$8") (pintype "bidirectional"))
      (node (ref "U$1") (pin "P$10") (pinfunction "10_P$10") (pintype "bidirectional"))
      (node (ref "U$1") (pin "P$100") (pinfunction "100_P$100") (pintype "bidirectional"))
      (node (ref "U$1") (pin "P$104") (pinfunction "104_P$104") (pintype "bidirectional"))
      (node (ref "U$1") (pin "P$110") (pinfunction "110_P$110") (pintype "bidirectional"))
      (node (ref "U$1") (pin "P$114") (pinfunction "114_P$114") (pintype "bidirectional"))
      (node (ref "U$1") (pin "P$129") (pinfunction "129_P$129") (pintype "bidirectional"))
      (node (ref "U$1") (pin "P$135") (pinfunction "135_P$135") (pintype "bidirectional"))
      (node (ref "U$1") (pin "P$140") (pinfunction "140_P$140") (pintype "bidirectional"))
      (node (ref "U$1") (pin "P$19") (pinfunction "19_P$19") (pintype "bidirectional"))
      (node (ref "U$1") (pin "P$27") (pinfunction "27_P$27") (pintype "bidirectional"))
      (node (ref "U$1") (pin "P$32") (pinfunction "32_P$32") (pintype "bidirectional"))
      (node (ref "U$1") (pin "P$51") (pinfunction "51_P$51") (pintype "bidirectional"))
      (node (ref "U$1") (pin "P$58") (pinfunction "58_P$58") (pintype "bidirectional"))
      (node (ref "U$1") (pin "P$6") (pinfunction "6_P$6") (pintype "bidirectional"))
      (node (ref "U$1") (pin "P$62") (pinfunction "62_P$62") (pintype "bidirectional"))
      (node (ref "U$1") (pin "P$87") (pinfunction "87_P$87") (pintype "bidirectional"))
      (node (ref "U$1") (pin "P$91") (pinfunction "91_P$91") (pintype "bidirectional"))
      (node (ref "U$1") (pin "P$95") (pinfunction "95_P$95") (pintype "bidirectional"))
      (node (ref "USB-UART_1") (pin "1") (pinfunction "1_1") (pintype "passive"))
      (node (ref "Y1") (pin "2") (pinfunction "GND_1_2") (pintype "bidirectional"))
      (node (ref "Y1") (pin "4") (pinfunction "GND_2_4") (pintype "bidirectional"))
    )
    (net (code "23") (name "IN_0.8") (class "Default")
      (node (ref "C1") (pin "1") (pinfunction "1_1") (pintype "passive"))
      (node (ref "IC1") (pin "6") (pinfunction "EN_6") (pintype "bidirectional"))
      (node (ref "IC1") (pin "7") (pinfunction "IN_1_7") (pintype "bidirectional"))
      (node (ref "IC1") (pin "8") (pinfunction "IN_2_8") (pintype "bidirectional"))
    )
    (net (code "24") (name "IN_1.2") (class "Default")
      (node (ref "C4") (pin "1") (pinfunction "1_1") (pintype "passive"))
      (node (ref "IC2") (pin "6") (pinfunction "EN_6") (pintype "bidirectional"))
      (node (ref "IC2") (pin "7") (pinfunction "IN_1_7") (pintype "bidirectional"))
      (node (ref "IC2") (pin "8") (pinfunction "IN_2_8") (pintype "bidirectional"))
    )
    (net (code "25") (name "IN_3.3") (class "Default")
      (node (ref "C7") (pin "1") (pinfunction "1_1") (pintype "passive"))
      (node (ref "IC3") (pin "6") (pinfunction "EN_6") (pintype "bidirectional"))
      (node (ref "IC3") (pin "7") (pinfunction "IN_1_7") (pintype "bidirectional"))
      (node (ref "IC3") (pin "8") (pinfunction "IN_2_8") (pintype "bidirectional"))
      (node (ref "POWER_IN") (pin "2") (pinfunction "2_2") (pintype "passive"))
    )
    (net (code "26") (name "K_CLK") (class "Default")
      (node (ref "LEROS_FPGA") (pin "32") (pinfunction "32_32") (pintype "passive"))
      (node (ref "U$1") (pin "P$103") (pinfunction "103_P$103") (pintype "bidirectional"))
    )
    (net (code "27") (name "K_CPU_RST_N") (class "Default")
      (node (ref "K_CPU_RST") (pin "2") (pinfunction "2_2") (pintype "passive"))
      (node (ref "U$1") (pin "P$113") (pinfunction "113_P$113") (pintype "bidirectional"))
    )
    (net (code "28") (name "K_CPU_RST_N_FPGA") (class "Default")
      (node (ref "K_CPU_RST") (pin "1") (pinfunction "1_1") (pintype "passive"))
      (node (ref "LEROS_FPGA") (pin "31") (pinfunction "31_31") (pintype "passive"))
    )
    (net (code "29") (name "K_FLASH_LOADED") (class "Default")
      (node (ref "LEROS_FPGA") (pin "2") (pinfunction "2_2") (pintype "passive"))
      (node (ref "U$1") (pin "P$25") (pinfunction "25_P$25") (pintype "bidirectional"))
    )
    (net (code "30") (name "K_FL_ADDR[0]") (class "Default")
      (node (ref "LEROS_FPGA") (pin "27") (pinfunction "27_27") (pintype "passive"))
      (node (ref "U$1") (pin "P$128") (pinfunction "128_P$128") (pintype "bidirectional"))
    )
    (net (code "31") (name "K_FL_ADDR[1]") (class "Default")
      (node (ref "LEROS_FPGA") (pin "26") (pinfunction "26_26") (pintype "passive"))
      (node (ref "U$1") (pin "P$130") (pinfunction "130_P$130") (pintype "bidirectional"))
    )
    (net (code "32") (name "K_FL_ADDR[2]") (class "Default")
      (node (ref "LEROS_FPGA") (pin "25") (pinfunction "25_25") (pintype "passive"))
      (node (ref "U$1") (pin "P$133") (pinfunction "133_P$133") (pintype "bidirectional"))
    )
    (net (code "33") (name "K_FL_ADDR[3]") (class "Default")
      (node (ref "LEROS_FPGA") (pin "24") (pinfunction "24_24") (pintype "passive"))
      (node (ref "U$1") (pin "P$137") (pinfunction "137_P$137") (pintype "bidirectional"))
    )
    (net (code "34") (name "K_FL_ADDR[4]") (class "Default")
      (node (ref "LEROS_FPGA") (pin "23") (pinfunction "23_23") (pintype "passive"))
      (node (ref "U$1") (pin "P$139") (pinfunction "139_P$139") (pintype "bidirectional"))
    )
    (net (code "35") (name "K_FL_ADDR[5]") (class "Default")
      (node (ref "LEROS_FPGA") (pin "22") (pinfunction "22_22") (pintype "passive"))
      (node (ref "U$1") (pin "P$141") (pinfunction "141_P$141") (pintype "bidirectional"))
    )
    (net (code "36") (name "K_FL_ADDR[6]") (class "Default")
      (node (ref "LEROS_FPGA") (pin "21") (pinfunction "21_21") (pintype "passive"))
      (node (ref "U$1") (pin "P$142") (pinfunction "142_P$142") (pintype "bidirectional"))
    )
    (net (code "37") (name "K_FL_ADDR[7]") (class "Default")
      (node (ref "LEROS_FPGA") (pin "20") (pinfunction "20_20") (pintype "passive"))
      (node (ref "U$1") (pin "P$143") (pinfunction "143_P$143") (pintype "bidirectional"))
    )
    (net (code "38") (name "K_FL_ADDR[8]") (class "Default")
      (node (ref "LEROS_FPGA") (pin "19") (pinfunction "19_19") (pintype "passive"))
      (node (ref "U$1") (pin "P$144") (pinfunction "144_P$144") (pintype "bidirectional"))
    )
    (net (code "39") (name "K_FL_ADDR[9]") (class "Default")
      (node (ref "LEROS_FPGA") (pin "18") (pinfunction "18_18") (pintype "passive"))
      (node (ref "U$1") (pin "P$145") (pinfunction "145_P$145") (pintype "bidirectional"))
    )
    (net (code "40") (name "K_FL_CE_N") (class "Default")
      (node (ref "LEROS_FPGA") (pin "7") (pinfunction "7_7") (pintype "passive"))
      (node (ref "U$1") (pin "P$9") (pinfunction "9_P$9") (pintype "bidirectional"))
    )
    (net (code "41") (name "K_FL_DATA[0]") (class "Default")
      (node (ref "LEROS_FPGA") (pin "17") (pinfunction "17_17") (pintype "passive"))
      (node (ref "U$1") (pin "P$147") (pinfunction "147_P$147") (pintype "bidirectional"))
    )
    (net (code "42") (name "K_FL_DATA[1]") (class "Default")
      (node (ref "LEROS_FPGA") (pin "16") (pinfunction "16_16") (pintype "passive"))
      (node (ref "U$1") (pin "P$149") (pinfunction "149_P$149") (pintype "bidirectional"))
    )
    (net (code "43") (name "K_FL_DATA[2]") (class "Default")
      (node (ref "LEROS_FPGA") (pin "15") (pinfunction "15_15") (pintype "passive"))
      (node (ref "U$1") (pin "P$150") (pinfunction "150_P$150") (pintype "bidirectional"))
    )
    (net (code "44") (name "K_FL_DATA[3]") (class "Default")
      (node (ref "LEROS_FPGA") (pin "14") (pinfunction "14_14") (pintype "passive"))
      (node (ref "U$1") (pin "P$151") (pinfunction "151_P$151") (pintype "bidirectional"))
    )
    (net (code "45") (name "K_FL_DATA[4]") (class "Default")
      (node (ref "LEROS_FPGA") (pin "13") (pinfunction "13_13") (pintype "passive"))
      (node (ref "U$1") (pin "P$152") (pinfunction "152_P$152") (pintype "bidirectional"))
    )
    (net (code "46") (name "K_FL_DATA[5]") (class "Default")
      (node (ref "LEROS_FPGA") (pin "10") (pinfunction "10_10") (pintype "passive"))
      (node (ref "U$1") (pin "P$1") (pinfunction "1_P$1") (pintype "bidirectional"))
    )
    (net (code "47") (name "K_FL_DATA[6]") (class "Default")
      (node (ref "LEROS_FPGA") (pin "9") (pinfunction "9_9") (pintype "passive"))
      (node (ref "U$1") (pin "P$5") (pinfunction "5_P$5") (pintype "bidirectional"))
    )
    (net (code "48") (name "K_FL_DATA[7]") (class "Default")
      (node (ref "LEROS_FPGA") (pin "8") (pinfunction "8_8") (pintype "passive"))
      (node (ref "U$1") (pin "P$7") (pinfunction "7_P$7") (pintype "bidirectional"))
    )
    (net (code "49") (name "K_FL_OE_N") (class "Default")
      (node (ref "LEROS_FPGA") (pin "6") (pinfunction "6_6") (pintype "passive"))
      (node (ref "U$1") (pin "P$11") (pinfunction "11_P$11") (pintype "bidirectional"))
    )
    (net (code "50") (name "K_FL_RST_N") (class "Default")
      (node (ref "LEROS_FPGA") (pin "4") (pinfunction "4_4") (pintype "passive"))
      (node (ref "U$1") (pin "P$18") (pinfunction "18_P$18") (pintype "bidirectional"))
    )
    (net (code "51") (name "K_FL_WE_N") (class "Default")
      (node (ref "LEROS_FPGA") (pin "5") (pinfunction "5_5") (pintype "passive"))
      (node (ref "U$1") (pin "P$15") (pinfunction "15_P$15") (pintype "bidirectional"))
    )
    (net (code "52") (name "K_LEROS_RAM_1_VDD") (class "Default")
      (node (ref "C30") (pin "1") (pinfunction "1_1") (pintype "passive"))
      (node (ref "C31") (pin "1") (pinfunction "1_1") (pintype "passive"))
      (node (ref "LEROS") (pin "3") (pinfunction "3_3") (pintype "passive"))
      (node (ref "U$1") (pin "P$131") (pinfunction "131_P$131") (pintype "bidirectional"))
    )
    (net (code "53") (name "K_LEROS_RAM_2_VDD") (class "Default")
      (node (ref "C28") (pin "1") (pinfunction "1_1") (pintype "passive"))
      (node (ref "C29") (pin "1") (pinfunction "1_1") (pintype "passive"))
      (node (ref "LEROS") (pin "1") (pinfunction "1_1") (pintype "passive"))
      (node (ref "U$1") (pin "P$138") (pinfunction "138_P$138") (pintype "bidirectional"))
    )
    (net (code "54") (name "K_LEROS_VDD") (class "Default")
      (node (ref "C32") (pin "1") (pinfunction "1_1") (pintype "passive"))
      (node (ref "C33") (pin "1") (pinfunction "1_1") (pintype "passive"))
      (node (ref "LEROS") (pin "5") (pinfunction "5_5") (pintype "passive"))
      (node (ref "U$1") (pin "P$117") (pinfunction "117_P$117") (pintype "bidirectional"))
    )
    (net (code "55") (name "K_LOADER_RST_N") (class "Default")
      (node (ref "K_LOADED_RST") (pin "2") (pinfunction "2_2") (pintype "passive"))
      (node (ref "U$1") (pin "P$115") (pinfunction "115_P$115") (pintype "bidirectional"))
    )
    (net (code "56") (name "K_LOADER_RST_N_FPGA") (class "Default")
      (node (ref "K_LOADED_RST") (pin "1") (pinfunction "1_1") (pintype "passive"))
      (node (ref "LEROS_FPGA") (pin "28") (pinfunction "28_28") (pintype "passive"))
    )
    (net (code "57") (name "K_OLEDG[0]") (class "Default")
      (node (ref "JP6") (pin "2") (pinfunction "2_2") (pintype "passive"))
      (node (ref "U$1") (pin "P$119") (pinfunction "119_P$119") (pintype "bidirectional"))
    )
    (net (code "58") (name "K_SPI_CLK") (class "Default")
      (node (ref "LEROS_LORA") (pin "P$4") (pinfunction "SCK_P$4") (pintype "bidirectional"))
      (node (ref "U$1") (pin "P$20") (pinfunction "20_P$20") (pintype "bidirectional"))
    )
    (net (code "59") (name "K_SPI_CS_N") (class "Default")
      (node (ref "LEROS_LORA") (pin "P$5") (pinfunction "NSS_P$5") (pintype "bidirectional"))
      (node (ref "U$1") (pin "P$21") (pinfunction "21_P$21") (pintype "bidirectional"))
    )
    (net (code "60") (name "K_SPI_MISO") (class "Default")
      (node (ref "LEROS_LORA") (pin "P$2") (pinfunction "MISO_P$2") (pintype "bidirectional"))
      (node (ref "U$1") (pin "P$23") (pinfunction "23_P$23") (pintype "bidirectional"))
    )
    (net (code "61") (name "K_SPI_MOSI") (class "Default")
      (node (ref "LEROS_LORA") (pin "P$3") (pinfunction "MOSI_P$3") (pintype "bidirectional"))
      (node (ref "U$1") (pin "P$22") (pinfunction "22_P$22") (pintype "bidirectional"))
    )
    (net (code "62") (name "Net-(IC1-ADJ)") (class "Default")
      (node (ref "C2") (pin "2") (pinfunction "2_2") (pintype "passive"))
      (node (ref "IC1") (pin "3") (pinfunction "ADJ_3") (pintype "bidirectional"))
      (node (ref "R1") (pin "2") (pinfunction "2_2") (pintype "passive"))
      (node (ref "R2") (pin "2") (pinfunction "2_2") (pintype "passive"))
    )
    (net (code "63") (name "Net-(IC2-ADJ)") (class "Default")
      (node (ref "C5") (pin "2") (pinfunction "2_2") (pintype "passive"))
      (node (ref "IC2") (pin "3") (pinfunction "ADJ_3") (pintype "bidirectional"))
      (node (ref "R3") (pin "2") (pinfunction "2_2") (pintype "passive"))
      (node (ref "R4") (pin "2") (pinfunction "2_2") (pintype "passive"))
    )
    (net (code "64") (name "Net-(IC3-ADJ)") (class "Default")
      (node (ref "C8") (pin "2") (pinfunction "2_2") (pintype "passive"))
      (node (ref "IC3") (pin "3") (pinfunction "ADJ_3") (pintype "bidirectional"))
      (node (ref "R5") (pin "2") (pinfunction "2_2") (pintype "passive"))
      (node (ref "R6") (pin "2") (pinfunction "2_2") (pintype "passive"))
    )
    (net (code "65") (name "Net-(IC4-A)") (class "Default")
      (node (ref "C10") (pin "1") (pinfunction "1_1") (pintype "passive"))
      (node (ref "IC4") (pin "2") (pinfunction "A_2") (pintype "bidirectional"))
      (node (ref "R7") (pin "1") (pinfunction "1_1") (pintype "passive"))
      (node (ref "Y1") (pin "1") (pinfunction "CRYSTAL_1_1") (pintype "bidirectional"))
    )
    (net (code "66") (name "Net-(IC4-Y)") (class "Default")
      (node (ref "IC4") (pin "4") (pinfunction "Y_4") (pintype "bidirectional"))
      (node (ref "IC5") (pin "2") (pinfunction "A_2") (pintype "bidirectional"))
      (node (ref "R7") (pin "2") (pinfunction "2_2") (pintype "passive"))
      (node (ref "R8") (pin "2") (pinfunction "2_2") (pintype "passive"))
    )
    (net (code "67") (name "Net-(J1-Pad5)") (class "Default")
      (node (ref "J1") (pin "5") (pinfunction "5_5") (pintype "bidirectional"))
      (node (ref "RS_CLK") (pin "1") (pinfunction "1_1") (pintype "passive"))
    )
    (net (code "68") (name "Net-(J2-Pad5)") (class "Default")
      (node (ref "J2") (pin "5") (pinfunction "5_5") (pintype "bidirectional"))
      (node (ref "SERV_CLK") (pin "1") (pinfunction "1_1") (pintype "passive"))
    )
    (net (code "69") (name "Net-(JP6-Pad1)") (class "Default")
      (node (ref "JP6") (pin "1") (pinfunction "1_1") (pintype "passive"))
      (node (ref "LED2") (pin "A") (pinfunction "A_A") (pintype "passive"))
    )
    (net (code "70") (name "Net-(JP7-Pad1)") (class "Default")
      (node (ref "JP7") (pin "1") (pinfunction "1_1") (pintype "passive"))
      (node (ref "LED1") (pin "A") (pinfunction "A_A") (pintype "passive"))
    )
    (net (code "71") (name "Net-(LED1-PadC)") (class "Default")
      (node (ref "LED1") (pin "C") (pinfunction "C_C") (pintype "passive"))
      (node (ref "R12") (pin "2") (pinfunction "2_2") (pintype "passive"))
    )
    (net (code "72") (name "Net-(LED2-PadC)") (class "Default")
      (node (ref "LED2") (pin "C") (pinfunction "C_C") (pintype "passive"))
      (node (ref "R14") (pin "2") (pinfunction "2_2") (pintype "passive"))
    )
    (net (code "73") (name "Net-(LED3-PadC)") (class "Default")
      (node (ref "LED3") (pin "C") (pinfunction "C_C") (pintype "passive"))
      (node (ref "R10") (pin "2") (pinfunction "2_2") (pintype "passive"))
    )
    (net (code "74") (name "Net-(LED4-PadC)") (class "Default")
      (node (ref "LED4") (pin "C") (pinfunction "C_C") (pintype "passive"))
      (node (ref "R20") (pin "2") (pinfunction "2_2") (pintype "passive"))
    )
    (net (code "75") (name "Net-(LED5-PadC)") (class "Default")
      (node (ref "LED5") (pin "C") (pinfunction "C_C") (pintype "passive"))
      (node (ref "R18") (pin "2") (pinfunction "2_2") (pintype "passive"))
    )
    (net (code "76") (name "Net-(LED6-PadC)") (class "Default")
      (node (ref "LED6") (pin "C") (pinfunction "C_C") (pintype "passive"))
      (node (ref "R16") (pin "2") (pinfunction "2_2") (pintype "passive"))
    )
    (net (code "77") (name "Net-(LED7-PadC)") (class "Default")
      (node (ref "LED7") (pin "C") (pinfunction "C_C") (pintype "passive"))
      (node (ref "R17") (pin "2") (pinfunction "2_2") (pintype "passive"))
    )
    (net (code "78") (name "Net-(S1-COM)") (class "Default")
      (node (ref "R11") (pin "1") (pinfunction "1_1") (pintype "passive"))
      (node (ref "S1") (pin "2") (pinfunction "COM_2") (pintype "bidirectional"))
      (node (ref "SERV_RST") (pin "2") (pinfunction "2_2") (pintype "passive"))
    )
    (net (code "79") (name "Net-(S2-COM)") (class "Default")
      (node (ref "K_CPU_RST") (pin "3") (pinfunction "3_3") (pintype "passive"))
      (node (ref "R13") (pin "1") (pinfunction "1_1") (pintype "passive"))
      (node (ref "S2") (pin "2") (pinfunction "COM_2") (pintype "bidirectional"))
    )
    (net (code "80") (name "Net-(S3-COM)") (class "Default")
      (node (ref "K_LOADED_RST") (pin "3") (pinfunction "3_3") (pintype "passive"))
      (node (ref "R15") (pin "1") (pinfunction "1_1") (pintype "passive"))
      (node (ref "S3") (pin "2") (pinfunction "COM_2") (pintype "bidirectional"))
    )
    (net (code "81") (name "Net-(S4-COM)") (class "Default")
      (node (ref "R9") (pin "1") (pinfunction "1_1") (pintype "passive"))
      (node (ref "S4") (pin "2") (pinfunction "COM_2") (pintype "bidirectional"))
      (node (ref "SERV_RST1") (pin "2") (pinfunction "2_2") (pintype "passive"))
    )
    (net (code "82") (name "Net-(Y1-CRYSTAL_2)") (class "Default")
      (node (ref "C11") (pin "1") (pinfunction "1_1") (pintype "passive"))
      (node (ref "R8") (pin "1") (pinfunction "1_1") (pintype "passive"))
      (node (ref "Y1") (pin "3") (pinfunction "CRYSTAL_2_3") (pintype "bidirectional"))
    )
    (net (code "83") (name "OUT_0.8") (class "Default")
      (node (ref "C2") (pin "1") (pinfunction "1_1") (pintype "passive"))
      (node (ref "C3") (pin "1") (pinfunction "1_1") (pintype "passive"))
      (node (ref "CHIP") (pin "6") (pinfunction "6_6") (pintype "passive"))
      (node (ref "IC1") (pin "1") (pinfunction "OUT_1_1") (pintype "bidirectional"))
      (node (ref "IC1") (pin "2") (pinfunction "OUT_2_2") (pintype "bidirectional"))
      (node (ref "LED3") (pin "A") (pinfunction "A_A") (pintype "passive"))
      (node (ref "R1") (pin "1") (pinfunction "1_1") (pintype "passive"))
    )
    (net (code "84") (name "OUT_1.2") (class "Default")
      (node (ref "BIAS") (pin "2") (pinfunction "2_2") (pintype "passive"))
      (node (ref "BIAS") (pin "4") (pinfunction "4_4") (pintype "passive"))
      (node (ref "C5") (pin "1") (pinfunction "1_1") (pintype "passive"))
      (node (ref "C6") (pin "1") (pinfunction "1_1") (pintype "passive"))
      (node (ref "CHIP") (pin "8") (pinfunction "8_8") (pintype "passive"))
      (node (ref "IC2") (pin "1") (pinfunction "OUT_1_1") (pintype "bidirectional"))
      (node (ref "IC2") (pin "2") (pinfunction "OUT_2_2") (pintype "bidirectional"))
      (node (ref "LED4") (pin "A") (pinfunction "A_A") (pintype "passive"))
      (node (ref "LEROS") (pin "2") (pinfunction "2_2") (pintype "passive"))
      (node (ref "LEROS") (pin "4") (pinfunction "4_4") (pintype "passive"))
      (node (ref "LEROS") (pin "6") (pinfunction "6_6") (pintype "passive"))
      (node (ref "R3") (pin "1") (pinfunction "1_1") (pintype "passive"))
      (node (ref "SERV") (pin "2") (pinfunction "2_2") (pintype "passive"))
      (node (ref "SERV") (pin "4") (pinfunction "4_4") (pintype "passive"))
      (node (ref "TRNG") (pin "2") (pinfunction "2_2") (pintype "passive"))
      (node (ref "TRNG") (pin "4") (pinfunction "4_4") (pintype "passive"))
      (node (ref "TRNG") (pin "6") (pinfunction "6_6") (pintype "passive"))
    )
    (net (code "85") (name "OUT_3.3") (class "Default")
      (node (ref "C8") (pin "1") (pinfunction "1_1") (pintype "passive"))
      (node (ref "C9") (pin "1") (pinfunction "1_1") (pintype "passive"))
      (node (ref "CHIP") (pin "2") (pinfunction "2_2") (pintype "passive"))
      (node (ref "CHIP") (pin "4") (pinfunction "4_4") (pintype "passive"))
      (node (ref "IC3") (pin "1") (pinfunction "OUT_1_1") (pintype "bidirectional"))
      (node (ref "IC3") (pin "2") (pinfunction "OUT_2_2") (pintype "bidirectional"))
      (node (ref "LED5") (pin "A") (pinfunction "A_A") (pintype "passive"))
      (node (ref "R5") (pin "1") (pinfunction "1_1") (pintype "passive"))
    )
    (net (code "86") (name "RS_CHACHA_VDD") (class "Default")
      (node (ref "U$1") (pin "P$98") (pinfunction "98_P$98") (pintype "bidirectional"))
    )
    (net (code "87") (name "RS_CIT_VDD") (class "Default")
      (node (ref "U$1") (pin "P$112") (pinfunction "112_P$112") (pintype "bidirectional"))
    )
    (net (code "88") (name "RS_CLK") (class "Default")
      (node (ref "RS_CLK") (pin "2") (pinfunction "2_2") (pintype "passive"))
      (node (ref "U$1") (pin "P$83") (pinfunction "83_P$83") (pintype "bidirectional"))
    )
    (net (code "89") (name "RS_GPIO_I0") (class "Default")
      (node (ref "RS_GPIO") (pin "2") (pinfunction "2_2") (pintype "passive"))
      (node (ref "U$1") (pin "P$99") (pinfunction "99_P$99") (pintype "bidirectional"))
    )
    (net (code "90") (name "RS_GPI_O0") (class "Default")
      (node (ref "RS_GPIO") (pin "1") (pinfunction "1_1") (pintype "passive"))
      (node (ref "U$1") (pin "P$101") (pinfunction "101_P$101") (pintype "bidirectional"))
    )
    (net (code "91") (name "RS_QSPI_CLK") (class "Default")
      (node (ref "RS_FLASH") (pin "6") (pinfunction "6_6") (pintype "passive"))
      (node (ref "U$1") (pin "P$90") (pinfunction "90_P$90") (pintype "bidirectional"))
    )
    (net (code "92") (name "RS_QSPI_MISO") (class "Default")
      (node (ref "RS_FLASH") (pin "8") (pinfunction "8_8") (pintype "passive"))
      (node (ref "U$1") (pin "P$97") (pinfunction "97_P$97") (pintype "bidirectional"))
    )
    (net (code "93") (name "RS_QSPI_MOSI") (class "Default")
      (node (ref "RS_FLASH") (pin "10") (pinfunction "10_10") (pintype "passive"))
      (node (ref "U$1") (pin "P$93") (pinfunction "93_P$93") (pintype "bidirectional"))
    )
    (net (code "94") (name "RS_QSPI_SS") (class "Default")
      (node (ref "RS_FLASH") (pin "12") (pinfunction "12_12") (pintype "passive"))
      (node (ref "U$1") (pin "P$88") (pinfunction "88_P$88") (pintype "bidirectional"))
    )
    (net (code "95") (name "RS_RST") (class "Default")
      (node (ref "SERV_RST1") (pin "1") (pinfunction "1_1") (pintype "passive"))
      (node (ref "U$1") (pin "P$86") (pinfunction "86_P$86") (pintype "bidirectional"))
    )
    (net (code "96") (name "RS_TRNG_RO_REF") (class "Default")
      (node (ref "RS_TRNG") (pin "1") (pinfunction "1_1") (pintype "passive"))
      (node (ref "U$1") (pin "P$111") (pinfunction "111_P$111") (pintype "bidirectional"))
    )
    (net (code "97") (name "RS_TRNG_RO_RNG") (class "Default")
      (node (ref "RS_TRNG") (pin "2") (pinfunction "2_2") (pintype "passive"))
      (node (ref "U$1") (pin "P$109") (pinfunction "109_P$109") (pintype "bidirectional"))
    )
    (net (code "98") (name "RS_TRNG_RO_STOP") (class "Default")
      (node (ref "RS_TRNG") (pin "3") (pinfunction "3_3") (pintype "passive"))
      (node (ref "U$1") (pin "P$105") (pinfunction "105_P$105") (pintype "bidirectional"))
    )
    (net (code "99") (name "RS_TRNG_VDD") (class "Default")
      (node (ref "C36") (pin "1") (pinfunction "1_1") (pintype "passive"))
      (node (ref "C37") (pin "1") (pinfunction "1_1") (pintype "passive"))
      (node (ref "TRNG") (pin "3") (pinfunction "3_3") (pintype "passive"))
      (node (ref "U$1") (pin "P$102") (pinfunction "102_P$102") (pintype "bidirectional"))
    )
    (net (code "100") (name "RS_VDD") (class "Default")
      (node (ref "C38") (pin "1") (pinfunction "1_1") (pintype "passive"))
      (node (ref "C39") (pin "1") (pinfunction "1_1") (pintype "passive"))
      (node (ref "TRNG") (pin "5") (pinfunction "5_5") (pintype "passive"))
      (node (ref "U$1") (pin "P$89") (pinfunction "89_P$89") (pintype "bidirectional"))
    )
    (net (code "101") (name "VBN") (class "Default")
      (node (ref "BIAS") (pin "5") (pinfunction "5_5") (pintype "passive"))
      (node (ref "C16") (pin "1") (pinfunction "1_1") (pintype "passive"))
      (node (ref "C17") (pin "1") (pinfunction "1_1") (pintype "passive"))
      (node (ref "U$1") (pin "P$34") (pinfunction "34_P$34") (pintype "bidirectional"))
    )
    (net (code "102") (name "VBP") (class "Default")
      (node (ref "BIAS") (pin "3") (pinfunction "3_3") (pintype "passive"))
      (node (ref "C14") (pin "1") (pinfunction "1_1") (pintype "passive"))
      (node (ref "C15") (pin "1") (pinfunction "1_1") (pintype "passive"))
      (node (ref "U$1") (pin "P$37") (pinfunction "37_P$37") (pintype "bidirectional"))
    )
    (net (code "103") (name "VCCQ") (class "Default")
      (node (ref "C18") (pin "1") (pinfunction "1_1") (pintype "passive"))
      (node (ref "C19") (pin "1") (pinfunction "1_1") (pintype "passive"))
      (node (ref "CHIP") (pin "3") (pinfunction "3_3") (pintype "passive"))
      (node (ref "U$1") (pin "P$17") (pinfunction "17_P$17") (pintype "bidirectional"))
      (node (ref "U$1") (pin "P$3") (pinfunction "3_P$3") (pintype "bidirectional"))
      (node (ref "U$1") (pin "P$30") (pinfunction "30_P$30") (pintype "bidirectional"))
      (node (ref "U$1") (pin "P$49") (pinfunction "49_P$49") (pintype "bidirectional"))
      (node (ref "U$1") (pin "P$64") (pinfunction "64_P$64") (pintype "bidirectional"))
      (node (ref "U$1") (pin "P$85") (pinfunction "85_P$85") (pintype "bidirectional"))
    )
    (net (code "104") (name "VDD") (class "Default")
      (node (ref "BIAS") (pin "1") (pinfunction "1_1") (pintype "passive"))
      (node (ref "C12") (pin "1") (pinfunction "1_1") (pintype "passive"))
      (node (ref "C13") (pin "1") (pinfunction "1_1") (pintype "passive"))
      (node (ref "U$1") (pin "P$55") (pinfunction "55_P$55") (pintype "bidirectional"))
    )
    (net (code "105") (name "VDDA") (class "Default")
      (node (ref "C34") (pin "1") (pinfunction "1_1") (pintype "passive"))
      (node (ref "C35") (pin "1") (pinfunction "1_1") (pintype "passive"))
      (node (ref "TRNG") (pin "1") (pinfunction "1_1") (pintype "passive"))
      (node (ref "U$1") (pin "P$107") (pinfunction "107_P$107") (pintype "bidirectional"))
    )
    (net (code "106") (name "VDDH") (class "Default")
      (node (ref "C22") (pin "1") (pinfunction "1_1") (pintype "passive"))
      (node (ref "C23") (pin "1") (pinfunction "1_1") (pintype "passive"))
      (node (ref "CHIP") (pin "7") (pinfunction "7_7") (pintype "passive"))
      (node (ref "U$1") (pin "P$8") (pinfunction "8_P$8") (pintype "bidirectional"))
    )
    (net (code "107") (name "VDDLS") (class "Default")
      (node (ref "C20") (pin "1") (pinfunction "1_1") (pintype "passive"))
      (node (ref "C21") (pin "1") (pinfunction "1_1") (pintype "passive"))
      (node (ref "CHIP") (pin "5") (pinfunction "5_5") (pintype "passive"))
      (node (ref "U$1") (pin "P$13") (pinfunction "13_P$13") (pintype "bidirectional"))
    )
    (net (code "108") (name "VDD_3.3V") (class "Default")
      (node (ref "ALL_JTAG") (pin "1") (pinfunction "1_1") (pintype "passive"))
      (node (ref "ALL_JTAG") (pin "2") (pinfunction "2_2") (pintype "passive"))
      (node (ref "CHIP") (pin "1") (pinfunction "1_1") (pintype "passive"))
      (node (ref "IC4") (pin "5") (pinfunction "VCC_5") (pintype "bidirectional"))
      (node (ref "IC5") (pin "5") (pinfunction "VCC_5") (pintype "power_in"))
      (node (ref "LEROS_LORA") (pin "P$12") (pinfunction "3.3V_P$12") (pintype "bidirectional"))
      (node (ref "R11") (pin "2") (pinfunction "2_2") (pintype "passive"))
      (node (ref "R13") (pin "2") (pinfunction "2_2") (pintype "passive"))
      (node (ref "R15") (pin "2") (pinfunction "2_2") (pintype "passive"))
      (node (ref "R9") (pin "2") (pinfunction "2_2") (pintype "passive"))
      (node (ref "RS_FLASH") (pin "1") (pinfunction "1_1") (pintype "passive"))
      (node (ref "RS_FLASH") (pin "2") (pinfunction "2_2") (pintype "passive"))
      (node (ref "S1") (pin "1") (pinfunction "ON_1_1") (pintype "bidirectional"))
      (node (ref "S2") (pin "1") (pinfunction "ON_1_1") (pintype "bidirectional"))
      (node (ref "S3") (pin "1") (pinfunction "ON_1_1") (pintype "bidirectional"))
      (node (ref "S4") (pin "1") (pinfunction "ON_1_1") (pintype "bidirectional"))
      (node (ref "SERV_FLASH") (pin "1") (pinfunction "1_1") (pintype "passive"))
      (node (ref "SERV_FLASH") (pin "2") (pinfunction "2_2") (pintype "passive"))
      (node (ref "SERV_LORA") (pin "P$12") (pinfunction "3.3V_P$12") (pintype "bidirectional"))
      (node (ref "USB-UART_1") (pin "3") (pinfunction "3_3") (pintype "passive"))
    )
    (net (code "109") (name "VDD_3.3V_FPGA") (class "Default")
      (node (ref "LEROS_FPGA") (pin "29") (pinfunction "29_29") (pintype "passive"))
    )
    (net (code "110") (name "VDD_5V_FPGA") (class "Default")
      (node (ref "LED6") (pin "A") (pinfunction "A_A") (pintype "passive"))
      (node (ref "LEROS_FPGA") (pin "11") (pinfunction "11_11") (pintype "passive"))
      (node (ref "POWER_IN") (pin "3") (pinfunction "3_3") (pintype "passive"))
    )
    (net (code "111") (name "VDD_5V_UART") (class "Default")
      (node (ref "LED7") (pin "A") (pinfunction "A_A") (pintype "passive"))
      (node (ref "POWER_IN") (pin "1") (pinfunction "1_1") (pintype "passive"))
      (node (ref "USB-UART_2") (pin "2") (pinfunction "2_2") (pintype "passive"))
    )
    (net (code "112") (name "VSSQ") (class "Default")
      (node (ref "U$1") (pin "P$67") (pinfunction "67_P$67") (pintype "bidirectional"))
    )
    (net (code "113") (name "unconnected-(ALL_JTAG-Pad11)") (class "Default")
      (node (ref "ALL_JTAG") (pin "11") (pinfunction "11_11") (pintype "passive"))
    )
    (net (code "114") (name "unconnected-(ALL_JTAG-Pad15)") (class "Default")
      (node (ref "ALL_JTAG") (pin "15") (pinfunction "15_15") (pintype "passive"))
    )
    (net (code "115") (name "unconnected-(ALL_JTAG-Pad17)") (class "Default")
      (node (ref "ALL_JTAG") (pin "17") (pinfunction "17_17") (pintype "passive"))
    )
    (net (code "116") (name "unconnected-(ALL_JTAG-Pad19)") (class "Default")
      (node (ref "ALL_JTAG") (pin "19") (pinfunction "19_19") (pintype "passive"))
    )
    (net (code "117") (name "unconnected-(IC1-N{slash}C-Pad4)") (class "Default")
      (node (ref "IC1") (pin "4") (pinfunction "N/C_4") (pintype "no_connect"))
    )
    (net (code "118") (name "unconnected-(IC2-N{slash}C-Pad4)") (class "Default")
      (node (ref "IC2") (pin "4") (pinfunction "N/C_4") (pintype "no_connect"))
    )
    (net (code "119") (name "unconnected-(IC3-N{slash}C-Pad4)") (class "Default")
      (node (ref "IC3") (pin "4") (pinfunction "N/C_4") (pintype "no_connect"))
    )
    (net (code "120") (name "unconnected-(IC4-N.C..-Pad1)") (class "Default")
      (node (ref "IC4") (pin "1") (pinfunction "N.C.._1") (pintype "bidirectional"))
    )
    (net (code "121") (name "unconnected-(IC5-NC-Pad1)") (class "Default")
      (node (ref "IC5") (pin "1") (pinfunction "NC_1") (pintype "no_connect"))
    )
    (net (code "122") (name "unconnected-(LEROS_FPGA-Pad1)") (class "Default")
      (node (ref "LEROS_FPGA") (pin "1") (pinfunction "1_1") (pintype "passive"))
    )
    (net (code "123") (name "unconnected-(LEROS_FPGA-Pad3)") (class "Default")
      (node (ref "LEROS_FPGA") (pin "3") (pinfunction "3_3") (pintype "passive"))
    )
    (net (code "124") (name "unconnected-(LEROS_FPGA-Pad33)") (class "Default")
      (node (ref "LEROS_FPGA") (pin "33") (pinfunction "33_33") (pintype "passive"))
    )
    (net (code "125") (name "unconnected-(LEROS_FPGA-Pad34)") (class "Default")
      (node (ref "LEROS_FPGA") (pin "34") (pinfunction "34_34") (pintype "passive"))
    )
    (net (code "126") (name "unconnected-(LEROS_FPGA-Pad35)") (class "Default")
      (node (ref "LEROS_FPGA") (pin "35") (pinfunction "35_35") (pintype "passive"))
    )
    (net (code "127") (name "unconnected-(LEROS_FPGA-Pad36)") (class "Default")
      (node (ref "LEROS_FPGA") (pin "36") (pinfunction "36_36") (pintype "passive"))
    )
    (net (code "128") (name "unconnected-(LEROS_FPGA-Pad37)") (class "Default")
      (node (ref "LEROS_FPGA") (pin "37") (pinfunction "37_37") (pintype "passive"))
    )
    (net (code "129") (name "unconnected-(LEROS_FPGA-Pad38)") (class "Default")
      (node (ref "LEROS_FPGA") (pin "38") (pinfunction "38_38") (pintype "passive"))
    )
    (net (code "130") (name "unconnected-(LEROS_FPGA-Pad39)") (class "Default")
      (node (ref "LEROS_FPGA") (pin "39") (pinfunction "39_39") (pintype "passive"))
    )
    (net (code "131") (name "unconnected-(LEROS_FPGA-Pad40)") (class "Default")
      (node (ref "LEROS_FPGA") (pin "40") (pinfunction "40_40") (pintype "passive"))
    )
    (net (code "132") (name "unconnected-(LEROS_LORA-ANT-PadP$16)") (class "Default")
      (node (ref "LEROS_LORA") (pin "P$16") (pinfunction "ANT_P$16") (pintype "bidirectional"))
    )
    (net (code "133") (name "unconnected-(LEROS_LORA-DIO0-PadP$11)") (class "Default")
      (node (ref "LEROS_LORA") (pin "P$11") (pinfunction "DIO0_P$11") (pintype "bidirectional"))
    )
    (net (code "134") (name "unconnected-(LEROS_LORA-DIO1-PadP$10)") (class "Default")
      (node (ref "LEROS_LORA") (pin "P$10") (pinfunction "DIO1_P$10") (pintype "bidirectional"))
    )
    (net (code "135") (name "unconnected-(LEROS_LORA-DIO2-PadP$9)") (class "Default")
      (node (ref "LEROS_LORA") (pin "P$9") (pinfunction "DIO2_P$9") (pintype "bidirectional"))
    )
    (net (code "136") (name "unconnected-(LEROS_LORA-DIO3-PadP$14)") (class "Default")
      (node (ref "LEROS_LORA") (pin "P$14") (pinfunction "DIO3_P$14") (pintype "bidirectional"))
    )
    (net (code "137") (name "unconnected-(LEROS_LORA-DIO4-PadP$13)") (class "Default")
      (node (ref "LEROS_LORA") (pin "P$13") (pinfunction "DIO4_P$13") (pintype "bidirectional"))
    )
    (net (code "138") (name "unconnected-(LEROS_LORA-DIO5-PadP$7)") (class "Default")
      (node (ref "LEROS_LORA") (pin "P$7") (pinfunction "DIO5_P$7") (pintype "bidirectional"))
    )
    (net (code "139") (name "unconnected-(LEROS_LORA-RESET-PadP$6)") (class "Default")
      (node (ref "LEROS_LORA") (pin "P$6") (pinfunction "RESET_P$6") (pintype "bidirectional"))
    )
    (net (code "140") (name "unconnected-(RS_FLASH-Pad5)") (class "Default")
      (node (ref "RS_FLASH") (pin "5") (pinfunction "5_5") (pintype "passive"))
    )
    (net (code "141") (name "unconnected-(RS_FLASH-Pad7)") (class "Default")
      (node (ref "RS_FLASH") (pin "7") (pinfunction "7_7") (pintype "passive"))
    )
    (net (code "142") (name "unconnected-(RS_FLASH-Pad9)") (class "Default")
      (node (ref "RS_FLASH") (pin "9") (pinfunction "9_9") (pintype "passive"))
    )
    (net (code "143") (name "unconnected-(RS_FLASH-Pad11)") (class "Default")
      (node (ref "RS_FLASH") (pin "11") (pinfunction "11_11") (pintype "passive"))
    )
    (net (code "144") (name "unconnected-(SERV_FLASH-Pad5)") (class "Default")
      (node (ref "SERV_FLASH") (pin "5") (pinfunction "5_5") (pintype "passive"))
    )
    (net (code "145") (name "unconnected-(SERV_FLASH-Pad7)") (class "Default")
      (node (ref "SERV_FLASH") (pin "7") (pinfunction "7_7") (pintype "passive"))
    )
    (net (code "146") (name "unconnected-(SERV_FLASH-Pad9)") (class "Default")
      (node (ref "SERV_FLASH") (pin "9") (pinfunction "9_9") (pintype "passive"))
    )
    (net (code "147") (name "unconnected-(SERV_FLASH-Pad11)") (class "Default")
      (node (ref "SERV_FLASH") (pin "11") (pinfunction "11_11") (pintype "passive"))
    )
    (net (code "148") (name "unconnected-(SERV_LORA-ANT-PadP$16)") (class "Default")
      (node (ref "SERV_LORA") (pin "P$16") (pinfunction "ANT_P$16") (pintype "bidirectional"))
    )
    (net (code "149") (name "unconnected-(SERV_LORA-DIO0-PadP$11)") (class "Default")
      (node (ref "SERV_LORA") (pin "P$11") (pinfunction "DIO0_P$11") (pintype "bidirectional"))
    )
    (net (code "150") (name "unconnected-(SERV_LORA-DIO1-PadP$10)") (class "Default")
      (node (ref "SERV_LORA") (pin "P$10") (pinfunction "DIO1_P$10") (pintype "bidirectional"))
    )
    (net (code "151") (name "unconnected-(SERV_LORA-DIO2-PadP$9)") (class "Default")
      (node (ref "SERV_LORA") (pin "P$9") (pinfunction "DIO2_P$9") (pintype "bidirectional"))
    )
    (net (code "152") (name "unconnected-(SERV_LORA-DIO3-PadP$14)") (class "Default")
      (node (ref "SERV_LORA") (pin "P$14") (pinfunction "DIO3_P$14") (pintype "bidirectional"))
    )
    (net (code "153") (name "unconnected-(SERV_LORA-DIO4-PadP$13)") (class "Default")
      (node (ref "SERV_LORA") (pin "P$13") (pinfunction "DIO4_P$13") (pintype "bidirectional"))
    )
    (net (code "154") (name "unconnected-(SERV_LORA-DIO5-PadP$7)") (class "Default")
      (node (ref "SERV_LORA") (pin "P$7") (pinfunction "DIO5_P$7") (pintype "bidirectional"))
    )
    (net (code "155") (name "unconnected-(SERV_LORA-RESET-PadP$6)") (class "Default")
      (node (ref "SERV_LORA") (pin "P$6") (pinfunction "RESET_P$6") (pintype "bidirectional"))
    )
    (net (code "156") (name "unconnected-(U$1-2-PadP$2)") (class "Default")
      (node (ref "U$1") (pin "P$2") (pinfunction "2_P$2") (pintype "bidirectional"))
    )
    (net (code "157") (name "unconnected-(U$1-4-PadP$4)") (class "Default")
      (node (ref "U$1") (pin "P$4") (pinfunction "4_P$4") (pintype "bidirectional"))
    )
    (net (code "158") (name "unconnected-(U$1-12-PadP$12)") (class "Default")
      (node (ref "U$1") (pin "P$12") (pinfunction "12_P$12") (pintype "bidirectional"))
    )
    (net (code "159") (name "unconnected-(U$1-14-PadP$14)") (class "Default")
      (node (ref "U$1") (pin "P$14") (pinfunction "14_P$14") (pintype "bidirectional"))
    )
    (net (code "160") (name "unconnected-(U$1-16-PadP$16)") (class "Default")
      (node (ref "U$1") (pin "P$16") (pinfunction "16_P$16") (pintype "bidirectional"))
    )
    (net (code "161") (name "unconnected-(U$1-26-PadP$26)") (class "Default")
      (node (ref "U$1") (pin "P$26") (pinfunction "26_P$26") (pintype "bidirectional"))
    )
    (net (code "162") (name "unconnected-(U$1-28-PadP$28)") (class "Default")
      (node (ref "U$1") (pin "P$28") (pinfunction "28_P$28") (pintype "bidirectional"))
    )
    (net (code "163") (name "unconnected-(U$1-36-PadP$36)") (class "Default")
      (node (ref "U$1") (pin "P$36") (pinfunction "36_P$36") (pintype "bidirectional"))
    )
    (net (code "164") (name "unconnected-(U$1-38-PadP$38)") (class "Default")
      (node (ref "U$1") (pin "P$38") (pinfunction "38_P$38") (pintype "bidirectional"))
    )
    (net (code "165") (name "unconnected-(U$1-40-PadP$40)") (class "Default")
      (node (ref "U$1") (pin "P$40") (pinfunction "40_P$40") (pintype "bidirectional"))
    )
    (net (code "166") (name "unconnected-(U$1-41-PadP$41)") (class "Default")
      (node (ref "U$1") (pin "P$41") (pinfunction "41_P$41") (pintype "bidirectional"))
    )
    (net (code "167") (name "unconnected-(U$1-42-PadP$42)") (class "Default")
      (node (ref "U$1") (pin "P$42") (pinfunction "42_P$42") (pintype "bidirectional"))
    )
    (net (code "168") (name "unconnected-(U$1-43-PadP$43)") (class "Default")
      (node (ref "U$1") (pin "P$43") (pinfunction "43_P$43") (pintype "bidirectional"))
    )
    (net (code "169") (name "unconnected-(U$1-44-PadP$44)") (class "Default")
      (node (ref "U$1") (pin "P$44") (pinfunction "44_P$44") (pintype "bidirectional"))
    )
    (net (code "170") (name "unconnected-(U$1-45-PadP$45)") (class "Default")
      (node (ref "U$1") (pin "P$45") (pinfunction "45_P$45") (pintype "bidirectional"))
    )
    (net (code "171") (name "unconnected-(U$1-46-PadP$46)") (class "Default")
      (node (ref "U$1") (pin "P$46") (pinfunction "46_P$46") (pintype "bidirectional"))
    )
    (net (code "172") (name "unconnected-(U$1-47-PadP$47)") (class "Default")
      (node (ref "U$1") (pin "P$47") (pinfunction "47_P$47") (pintype "bidirectional"))
    )
    (net (code "173") (name "unconnected-(U$1-52-PadP$52)") (class "Default")
      (node (ref "U$1") (pin "P$52") (pinfunction "52_P$52") (pintype "bidirectional"))
    )
    (net (code "174") (name "unconnected-(U$1-54-PadP$54)") (class "Default")
      (node (ref "U$1") (pin "P$54") (pinfunction "54_P$54") (pintype "bidirectional"))
    )
    (net (code "175") (name "unconnected-(U$1-56-PadP$56)") (class "Default")
      (node (ref "U$1") (pin "P$56") (pinfunction "56_P$56") (pintype "bidirectional"))
    )
    (net (code "176") (name "unconnected-(U$1-66-PadP$66)") (class "Default")
      (node (ref "U$1") (pin "P$66") (pinfunction "66_P$66") (pintype "bidirectional"))
    )
    (net (code "177") (name "unconnected-(U$1-68-PadP$68)") (class "Default")
      (node (ref "U$1") (pin "P$68") (pinfunction "68_P$68") (pintype "bidirectional"))
    )
    (net (code "178") (name "unconnected-(U$1-73-PadP$73)") (class "Default")
      (node (ref "U$1") (pin "P$73") (pinfunction "73_P$73") (pintype "bidirectional"))
    )
    (net (code "179") (name "unconnected-(U$1-74-PadP$74)") (class "Default")
      (node (ref "U$1") (pin "P$74") (pinfunction "74_P$74") (pintype "bidirectional"))
    )
    (net (code "180") (name "unconnected-(U$1-75-PadP$75)") (class "Default")
      (node (ref "U$1") (pin "P$75") (pinfunction "75_P$75") (pintype "bidirectional"))
    )
    (net (code "181") (name "unconnected-(U$1-76-PadP$76)") (class "Default")
      (node (ref "U$1") (pin "P$76") (pinfunction "76_P$76") (pintype "bidirectional"))
    )
    (net (code "182") (name "unconnected-(U$1-77-PadP$77)") (class "Default")
      (node (ref "U$1") (pin "P$77") (pinfunction "77_P$77") (pintype "bidirectional"))
    )
    (net (code "183") (name "unconnected-(U$1-78-PadP$78)") (class "Default")
      (node (ref "U$1") (pin "P$78") (pinfunction "78_P$78") (pintype "bidirectional"))
    )
    (net (code "184") (name "unconnected-(U$1-79-PadP$79)") (class "Default")
      (node (ref "U$1") (pin "P$79") (pinfunction "79_P$79") (pintype "bidirectional"))
    )
    (net (code "185") (name "unconnected-(U$1-80-PadP$80)") (class "Default")
      (node (ref "U$1") (pin "P$80") (pinfunction "80_P$80") (pintype "bidirectional"))
    )
    (net (code "186") (name "unconnected-(U$1-82-PadP$82)") (class "Default")
      (node (ref "U$1") (pin "P$82") (pinfunction "82_P$82") (pintype "bidirectional"))
    )
    (net (code "187") (name "unconnected-(U$1-84-PadP$84)") (class "Default")
      (node (ref "U$1") (pin "P$84") (pinfunction "84_P$84") (pintype "bidirectional"))
    )
    (net (code "188") (name "unconnected-(U$1-92-PadP$92)") (class "Default")
      (node (ref "U$1") (pin "P$92") (pinfunction "92_P$92") (pintype "bidirectional"))
    )
    (net (code "189") (name "unconnected-(U$1-94-PadP$94)") (class "Default")
      (node (ref "U$1") (pin "P$94") (pinfunction "94_P$94") (pintype "bidirectional"))
    )
    (net (code "190") (name "unconnected-(U$1-96-PadP$96)") (class "Default")
      (node (ref "U$1") (pin "P$96") (pinfunction "96_P$96") (pintype "bidirectional"))
    )
    (net (code "191") (name "unconnected-(U$1-106-PadP$106)") (class "Default")
      (node (ref "U$1") (pin "P$106") (pinfunction "106_P$106") (pintype "bidirectional"))
    )
    (net (code "192") (name "unconnected-(U$1-108-PadP$108)") (class "Default")
      (node (ref "U$1") (pin "P$108") (pinfunction "108_P$108") (pintype "bidirectional"))
    )
    (net (code "193") (name "unconnected-(U$1-116-PadP$116)") (class "Default")
      (node (ref "U$1") (pin "P$116") (pinfunction "116_P$116") (pintype "bidirectional"))
    )
    (net (code "194") (name "unconnected-(U$1-118-PadP$118)") (class "Default")
      (node (ref "U$1") (pin "P$118") (pinfunction "118_P$118") (pintype "bidirectional"))
    )
    (net (code "195") (name "unconnected-(U$1-120-PadP$120)") (class "Default")
      (node (ref "U$1") (pin "P$120") (pinfunction "120_P$120") (pintype "bidirectional"))
    )
    (net (code "196") (name "unconnected-(U$1-121-PadP$121)") (class "Default")
      (node (ref "U$1") (pin "P$121") (pinfunction "121_P$121") (pintype "bidirectional"))
    )
    (net (code "197") (name "unconnected-(U$1-122-PadP$122)") (class "Default")
      (node (ref "U$1") (pin "P$122") (pinfunction "122_P$122") (pintype "bidirectional"))
    )
    (net (code "198") (name "unconnected-(U$1-123-PadP$123)") (class "Default")
      (node (ref "U$1") (pin "P$123") (pinfunction "123_P$123") (pintype "bidirectional"))
    )
    (net (code "199") (name "unconnected-(U$1-124-PadP$124)") (class "Default")
      (node (ref "U$1") (pin "P$124") (pinfunction "124_P$124") (pintype "bidirectional"))
    )
    (net (code "200") (name "unconnected-(U$1-125-PadP$125)") (class "Default")
      (node (ref "U$1") (pin "P$125") (pinfunction "125_P$125") (pintype "bidirectional"))
    )
    (net (code "201") (name "unconnected-(U$1-126-PadP$126)") (class "Default")
      (node (ref "U$1") (pin "P$126") (pinfunction "126_P$126") (pintype "bidirectional"))
    )
    (net (code "202") (name "unconnected-(U$1-127-PadP$127)") (class "Default")
      (node (ref "U$1") (pin "P$127") (pinfunction "127_P$127") (pintype "bidirectional"))
    )
    (net (code "203") (name "unconnected-(U$1-132-PadP$132)") (class "Default")
      (node (ref "U$1") (pin "P$132") (pinfunction "132_P$132") (pintype "bidirectional"))
    )
    (net (code "204") (name "unconnected-(U$1-134-PadP$134)") (class "Default")
      (node (ref "U$1") (pin "P$134") (pinfunction "134_P$134") (pintype "bidirectional"))
    )
    (net (code "205") (name "unconnected-(U$1-136-PadP$136)") (class "Default")
      (node (ref "U$1") (pin "P$136") (pinfunction "136_P$136") (pintype "bidirectional"))
    )
    (net (code "206") (name "unconnected-(U$1-146-PadP$146)") (class "Default")
      (node (ref "U$1") (pin "P$146") (pinfunction "146_P$146") (pintype "bidirectional"))
    )
    (net (code "207") (name "unconnected-(U$1-148-PadP$148)") (class "Default")
      (node (ref "U$1") (pin "P$148") (pinfunction "148_P$148") (pintype "bidirectional"))
    )
    (net (code "208") (name "unconnected-(U$1-153-PadP$153)") (class "Default")
      (node (ref "U$1") (pin "P$153") (pinfunction "153_P$153") (pintype "bidirectional"))
    )
    (net (code "209") (name "unconnected-(U$1-154-PadP$154)") (class "Default")
      (node (ref "U$1") (pin "P$154") (pinfunction "154_P$154") (pintype "bidirectional"))
    )
    (net (code "210") (name "unconnected-(U$1-155-PadP$155)") (class "Default")
      (node (ref "U$1") (pin "P$155") (pinfunction "155_P$155") (pintype "bidirectional"))
    )
    (net (code "211") (name "unconnected-(U$1-156-PadP$156)") (class "Default")
      (node (ref "U$1") (pin "P$156") (pinfunction "156_P$156") (pintype "bidirectional"))
    )
    (net (code "212") (name "unconnected-(U$1-157-PadP$157)") (class "Default")
      (node (ref "U$1") (pin "P$157") (pinfunction "157_P$157") (pintype "bidirectional"))
    )
    (net (code "213") (name "unconnected-(U$1-158-PadP$158)") (class "Default")
      (node (ref "U$1") (pin "P$158") (pinfunction "158_P$158") (pintype "bidirectional"))
    )
    (net (code "214") (name "unconnected-(U$1-159-PadP$159)") (class "Default")
      (node (ref "U$1") (pin "P$159") (pinfunction "159_P$159") (pintype "bidirectional"))
    )
    (net (code "215") (name "unconnected-(U$1-160-PadP$160)") (class "Default")
      (node (ref "U$1") (pin "P$160") (pinfunction "160_P$160") (pintype "bidirectional"))
    )
    (net (code "216") (name "unconnected-(USB-UART_2-Pad1)") (class "Default")
      (node (ref "USB-UART_2") (pin "1") (pinfunction "1_1") (pintype "passive"))
    )
    (net (code "217") (name "unconnected-(USB-UART_2-Pad3)") (class "Default")
      (node (ref "USB-UART_2") (pin "3") (pinfunction "3_3") (pintype "passive"))
    )
    (net (code "218") (name "unconnected-(USB-UART_2-Pad4)") (class "Default")
      (node (ref "USB-UART_2") (pin "4") (pinfunction "4_4") (pintype "passive"))
    )
  )
)
